# I2CRJ45X24.net
KiCad netlist of a schematic drawn in EAGLE
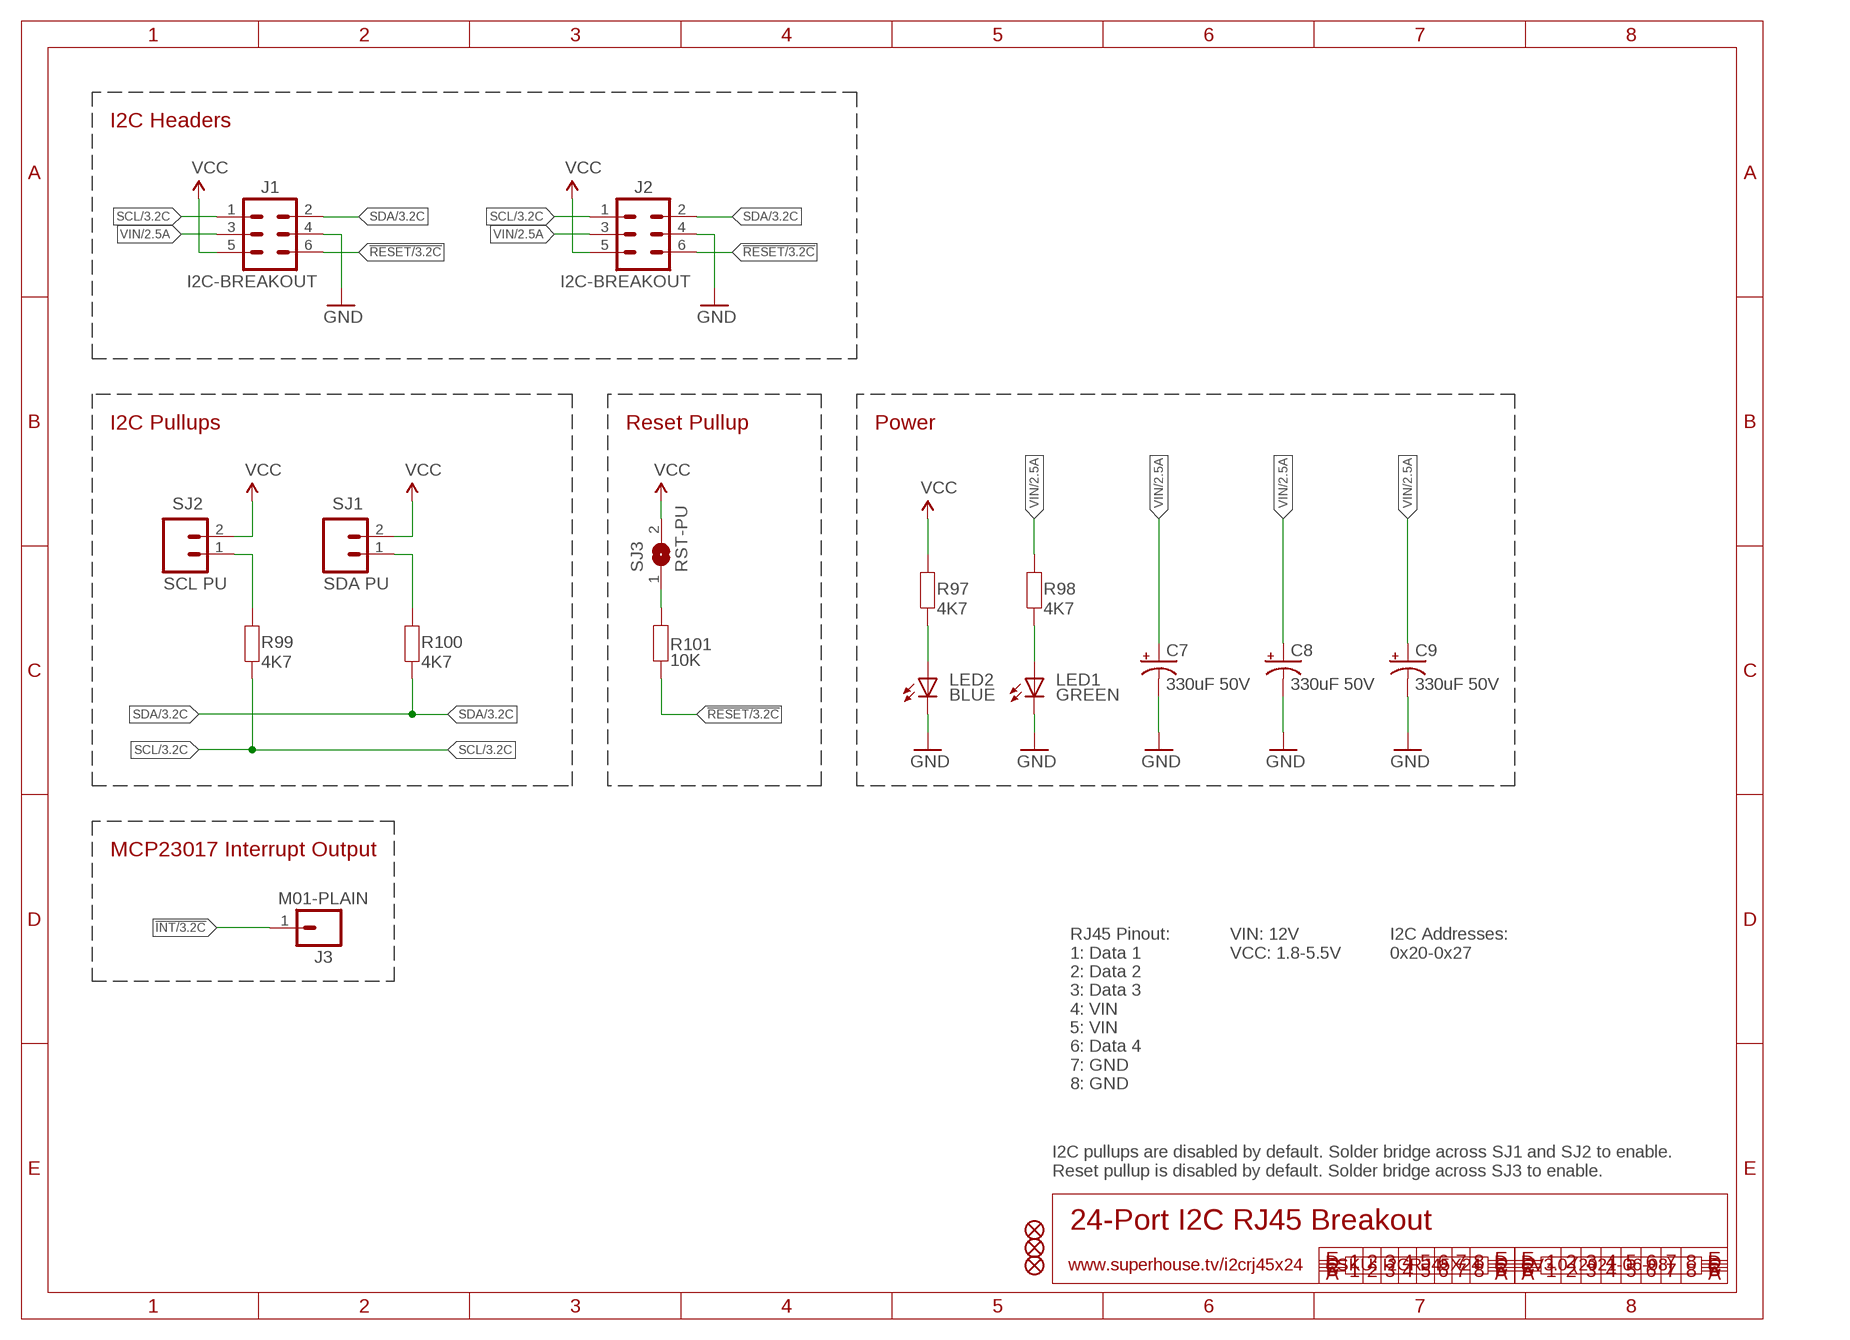
[diagram p0: schematic, sheet 1]
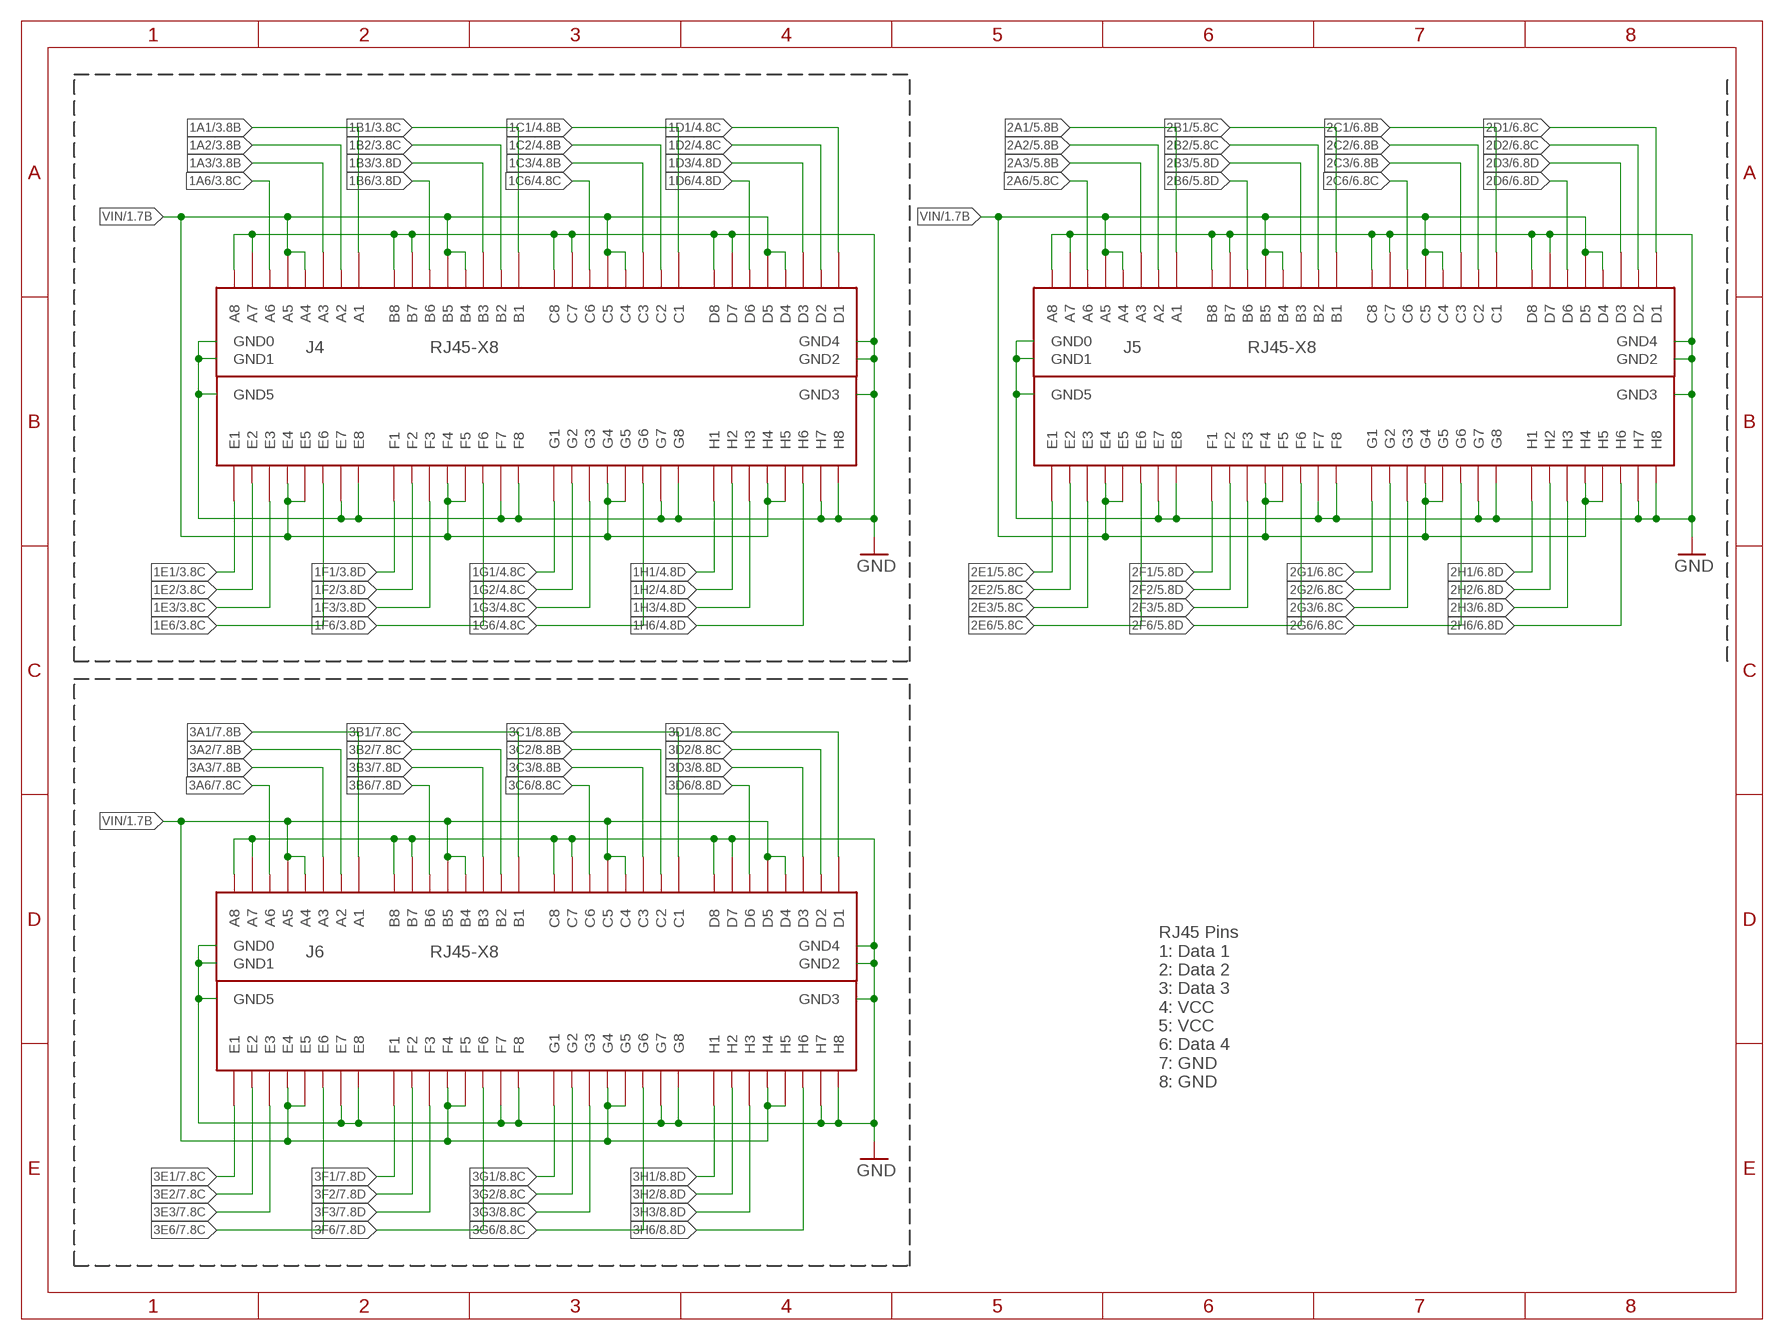
[diagram p1: schematic, sheet 2]
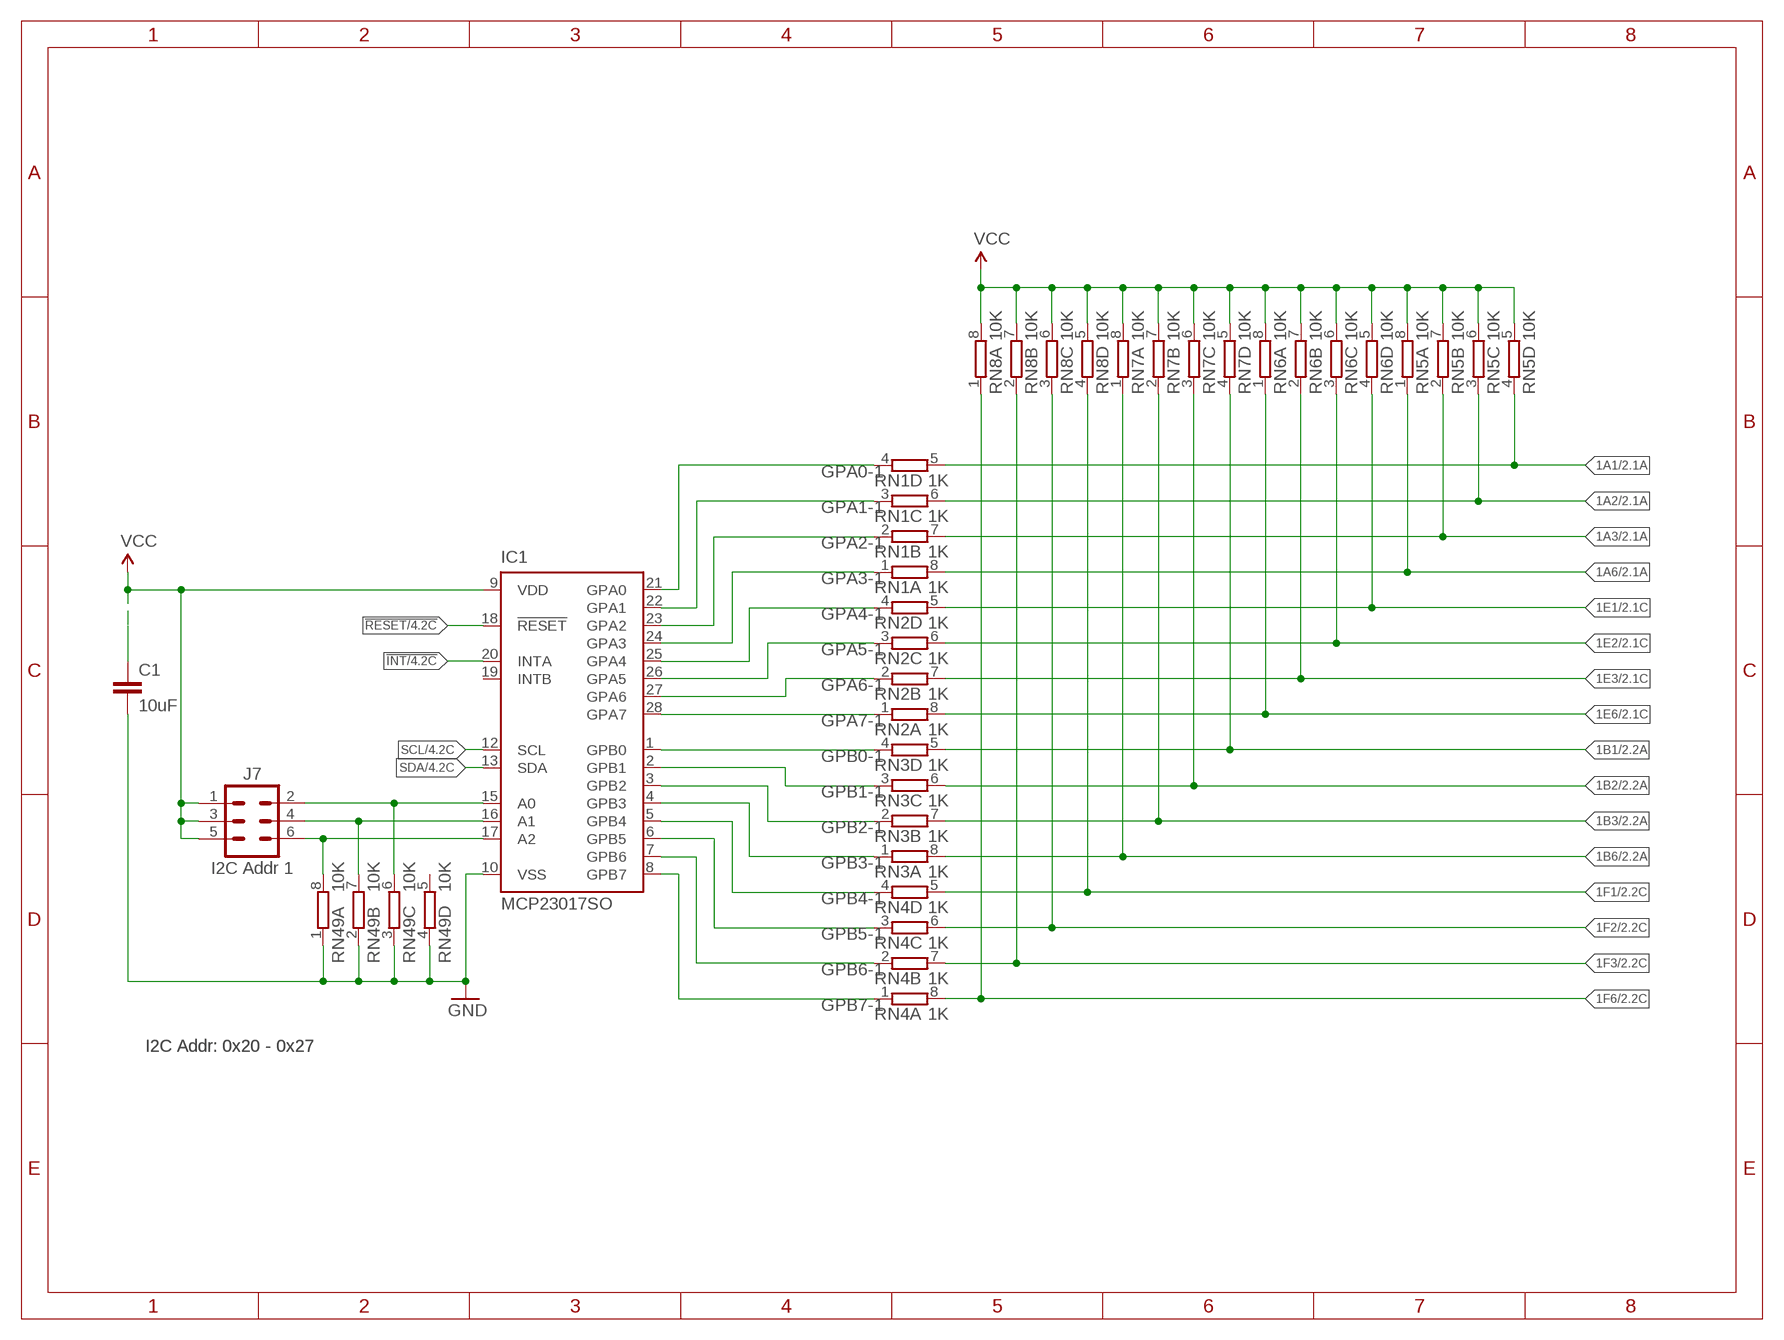
[diagram p2: schematic, sheet 3]
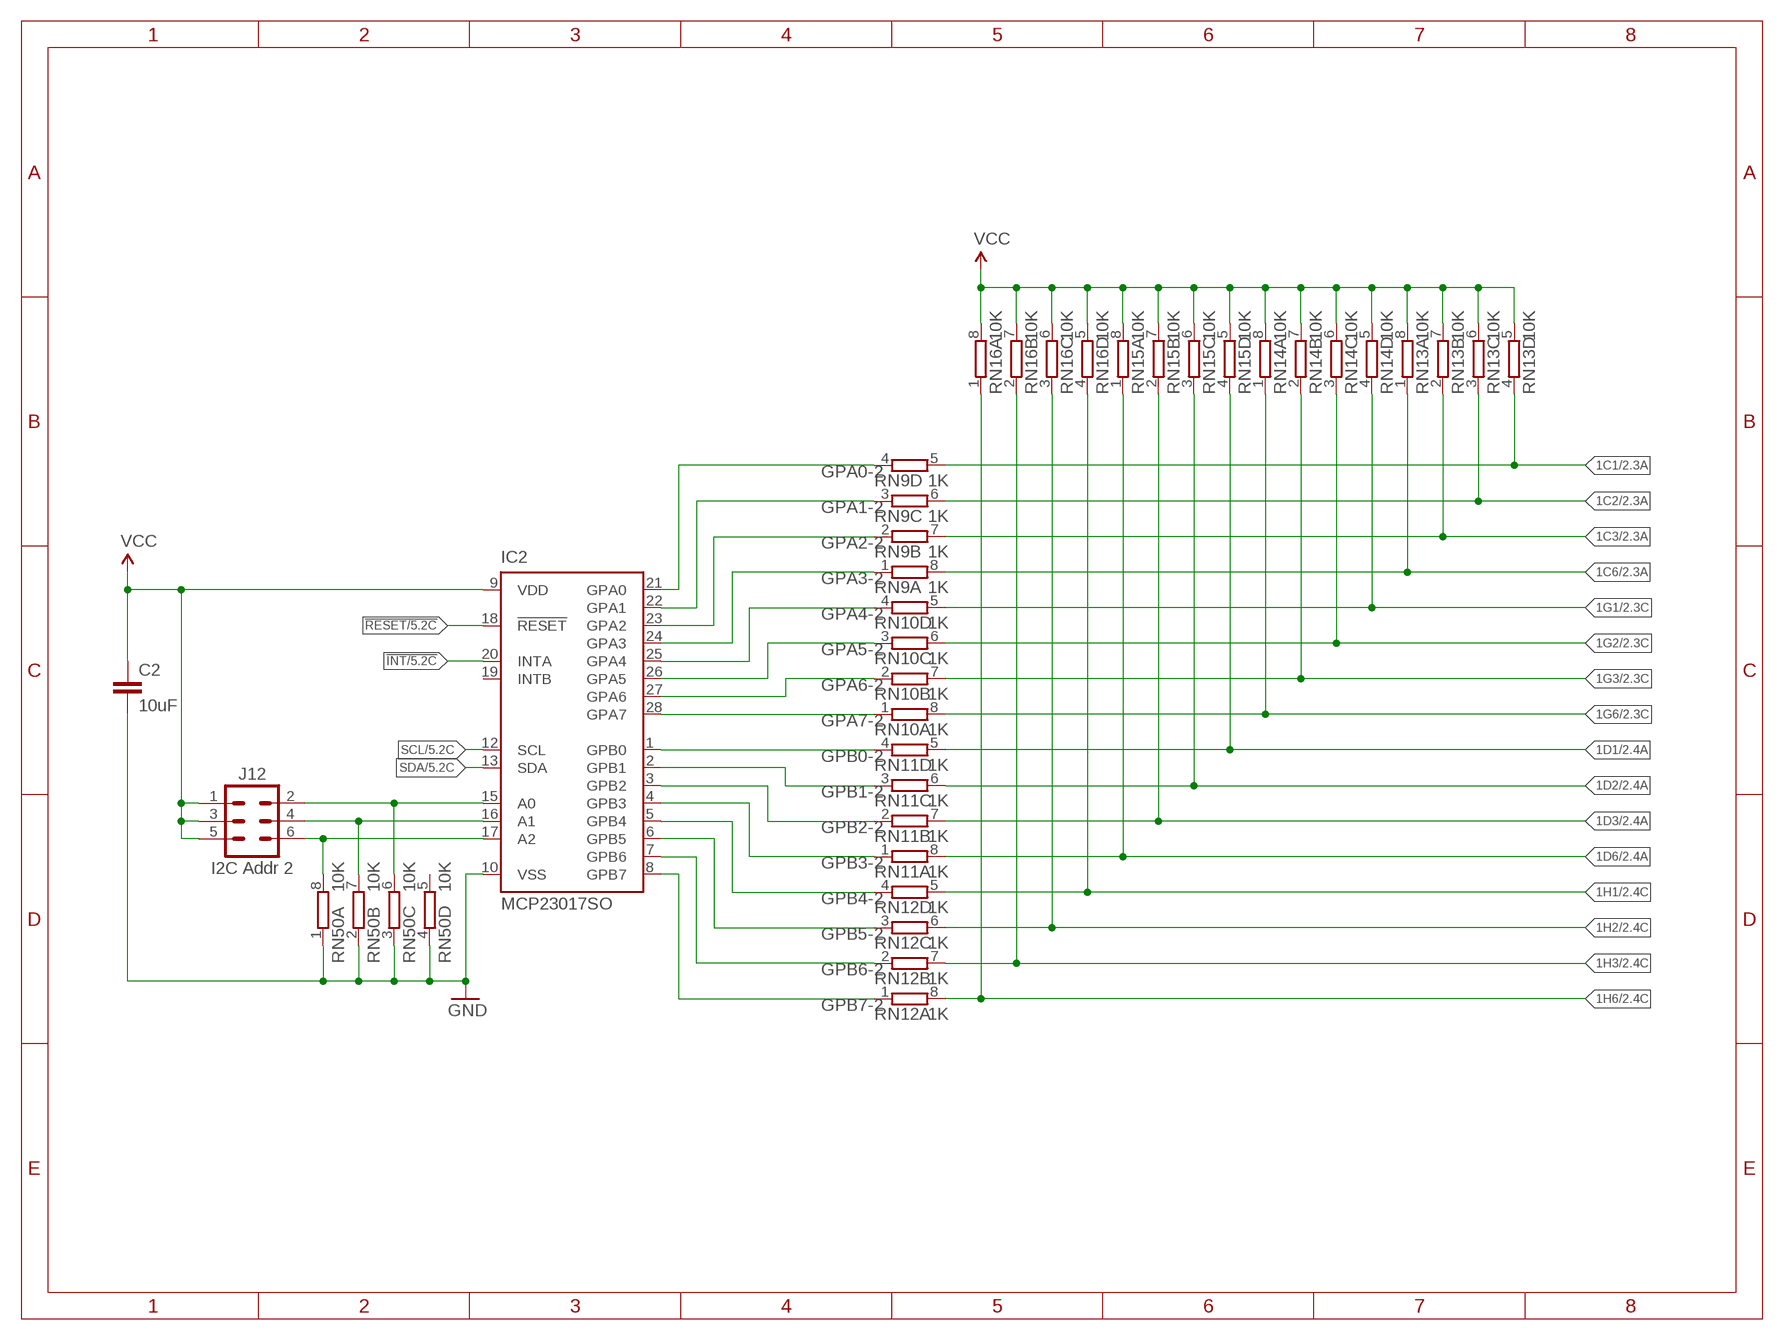
[diagram p3: schematic, sheet 4]
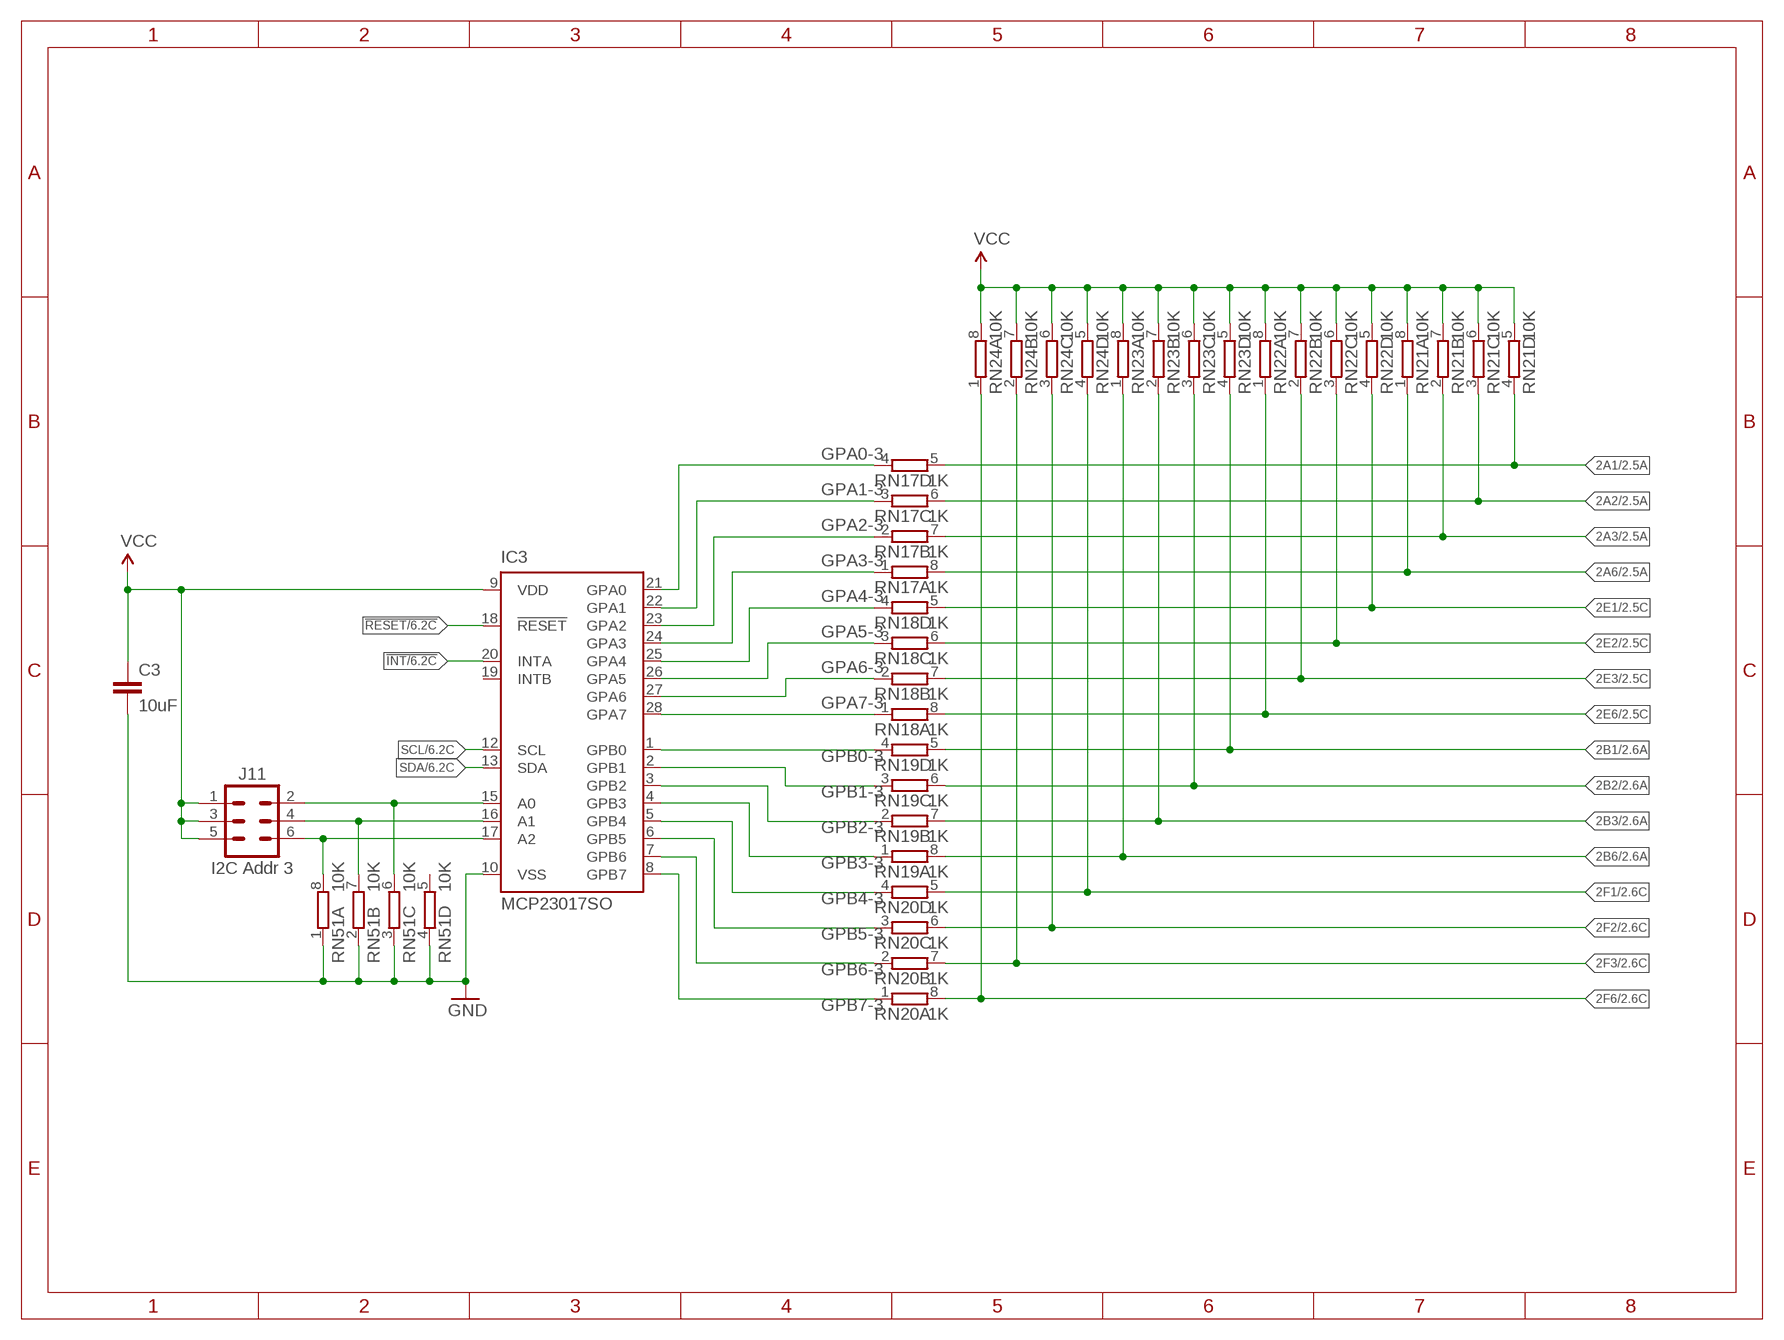
[diagram p4: schematic, sheet 5]
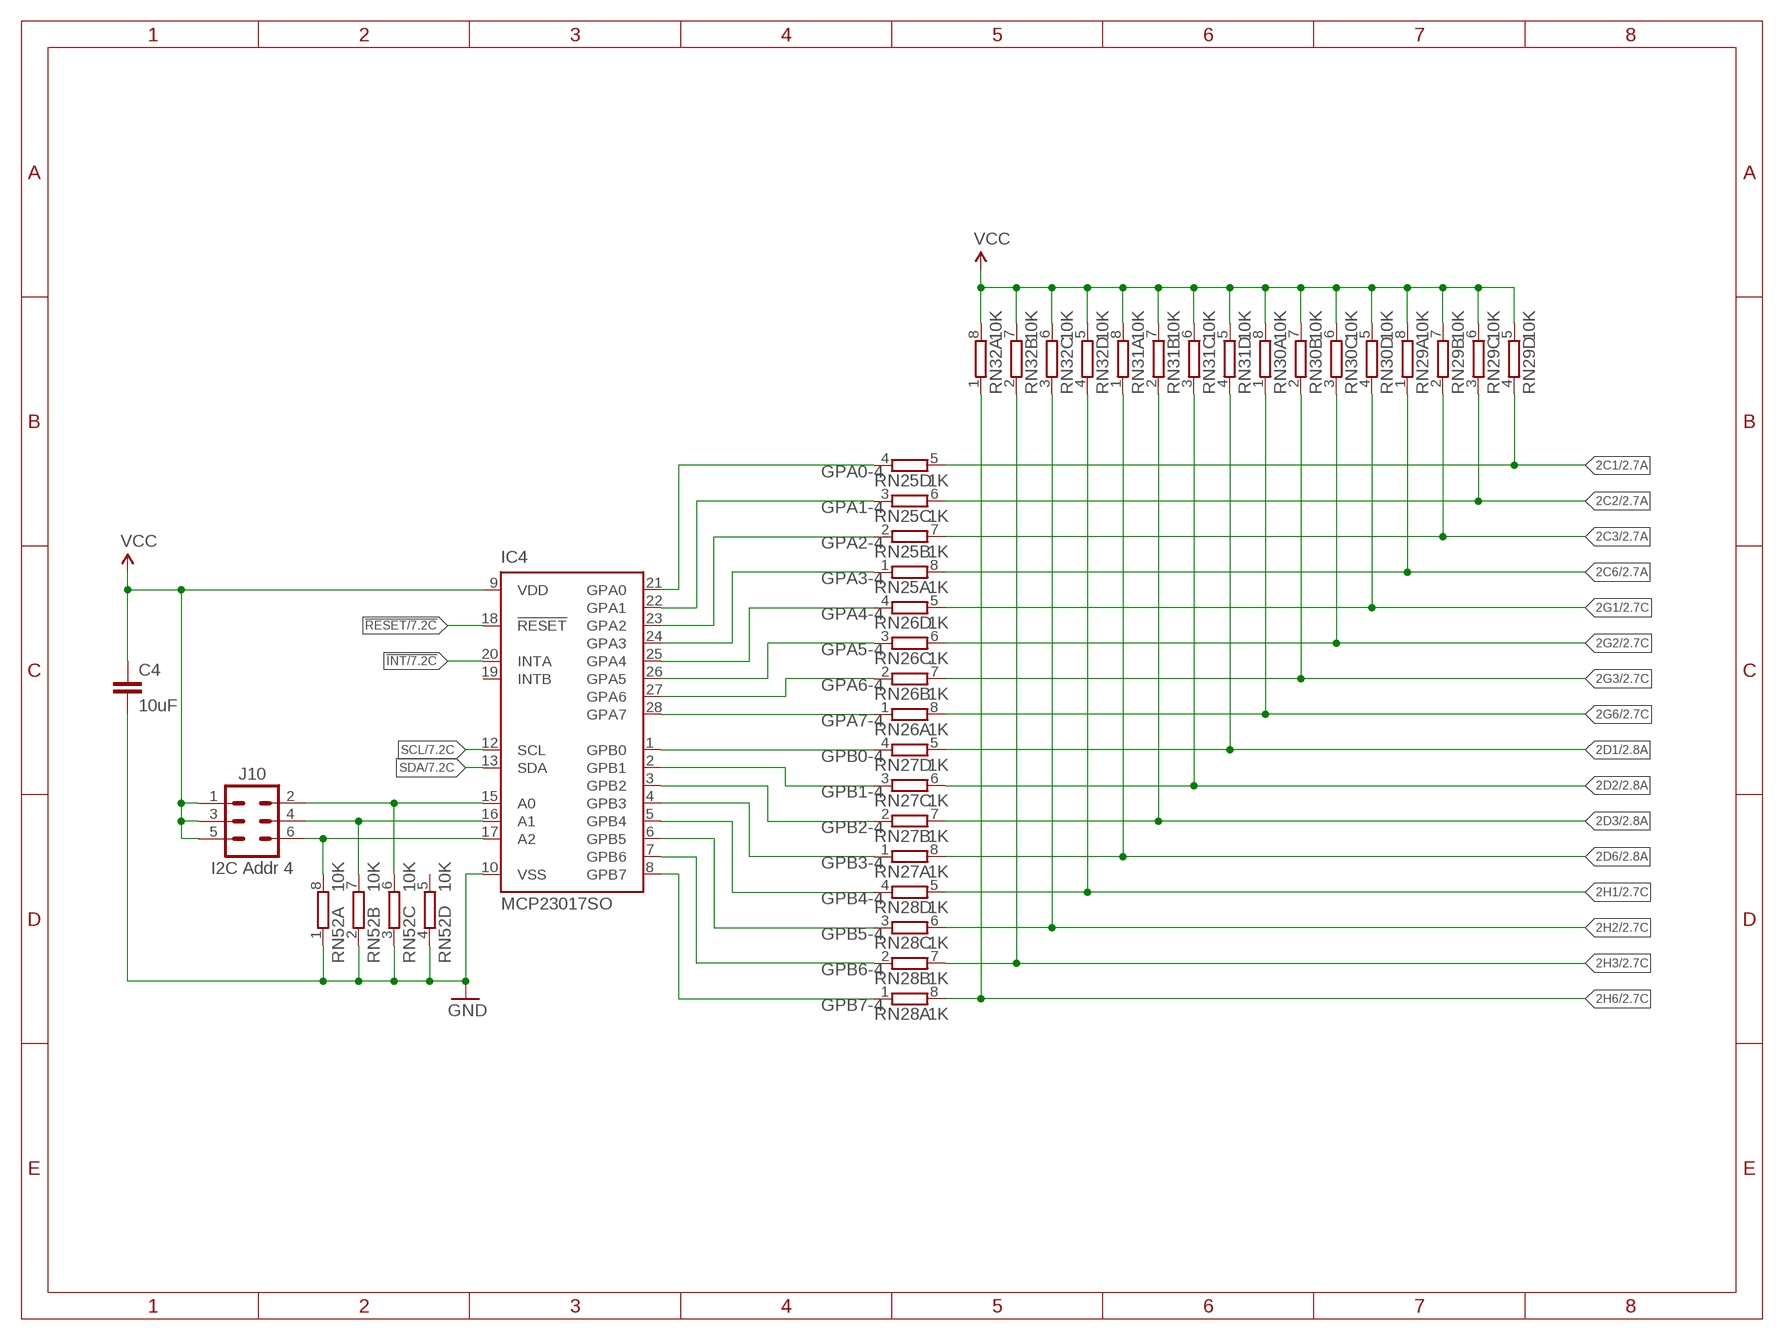
[diagram p5: schematic, sheet 6]
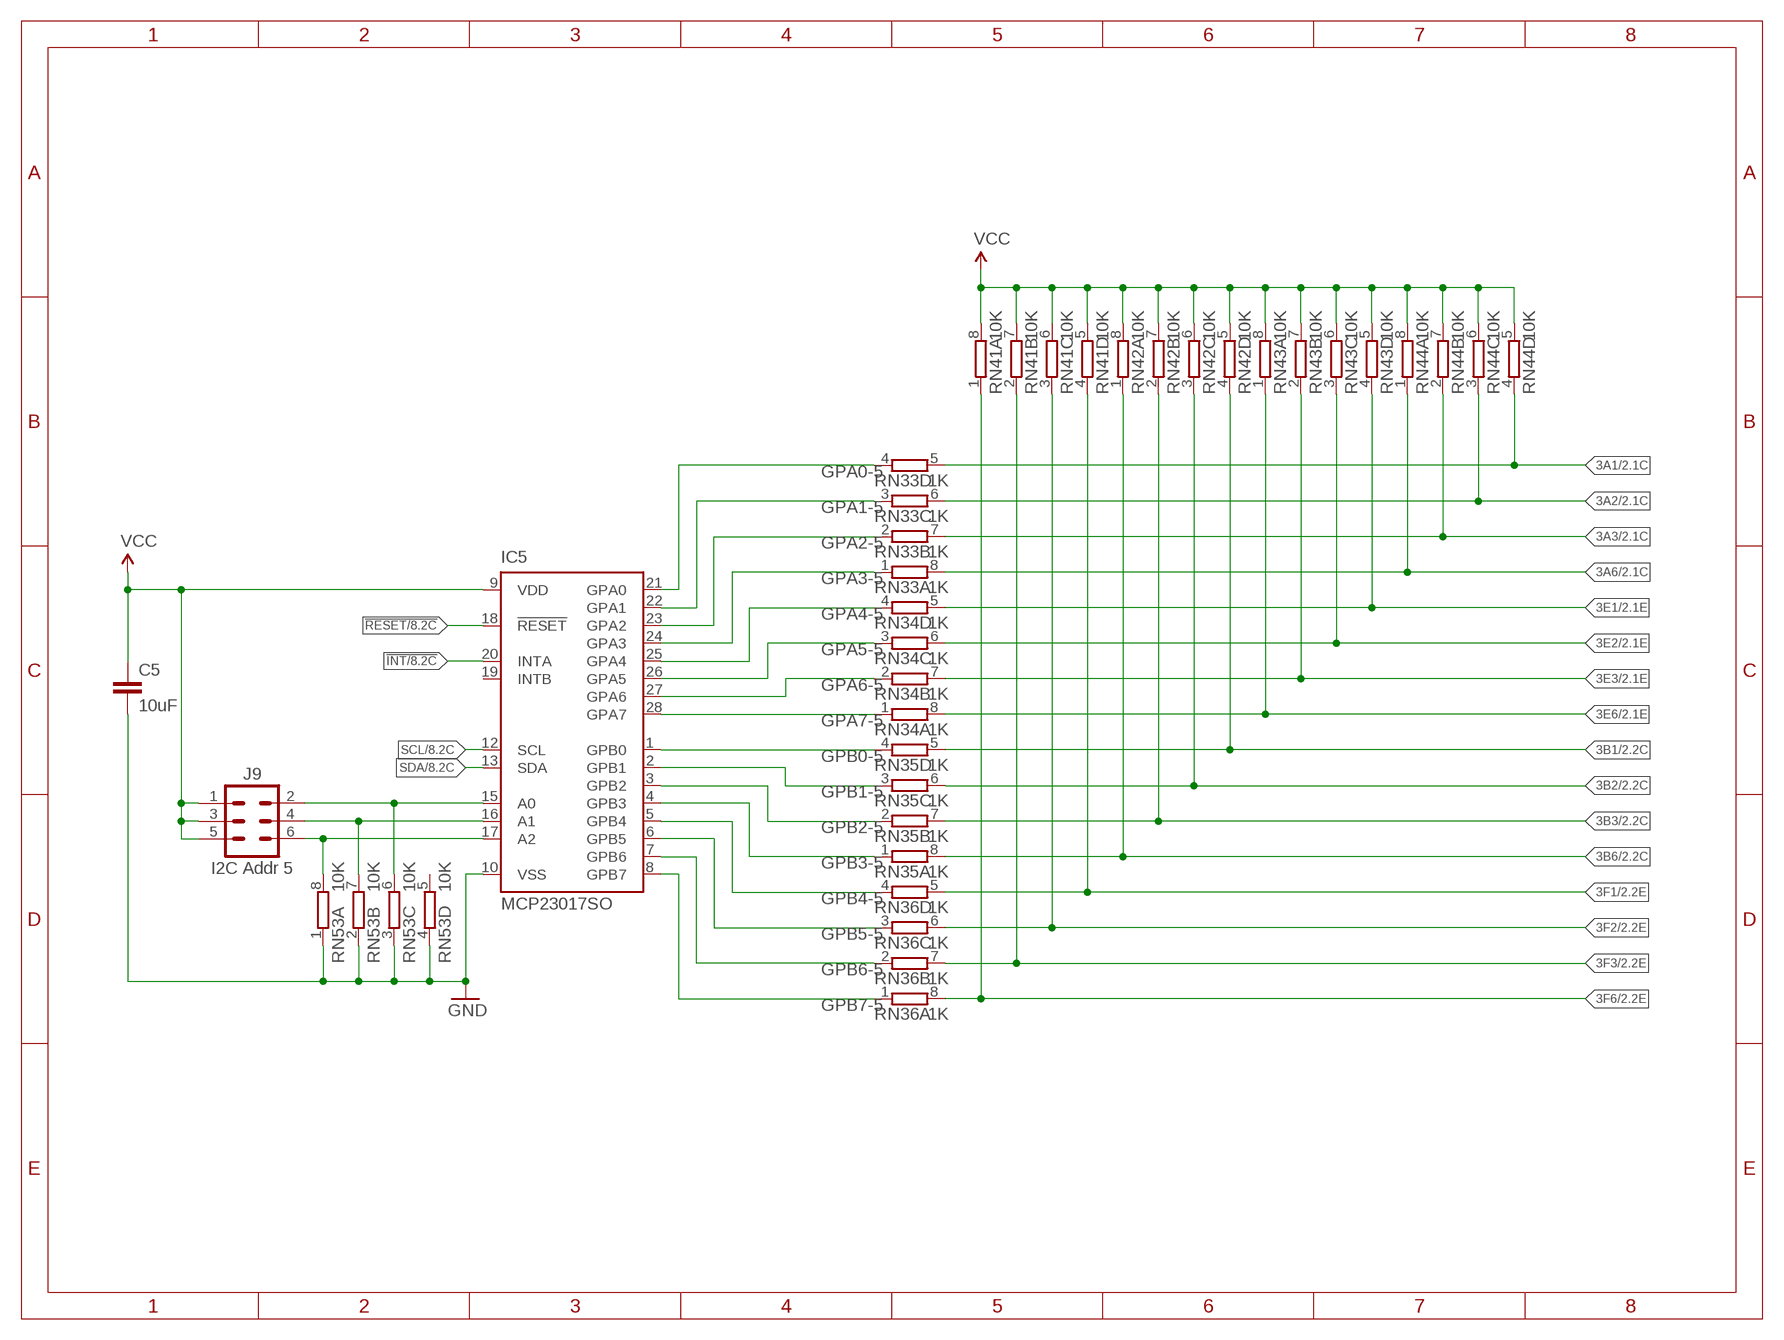
[diagram p6: schematic, sheet 7]
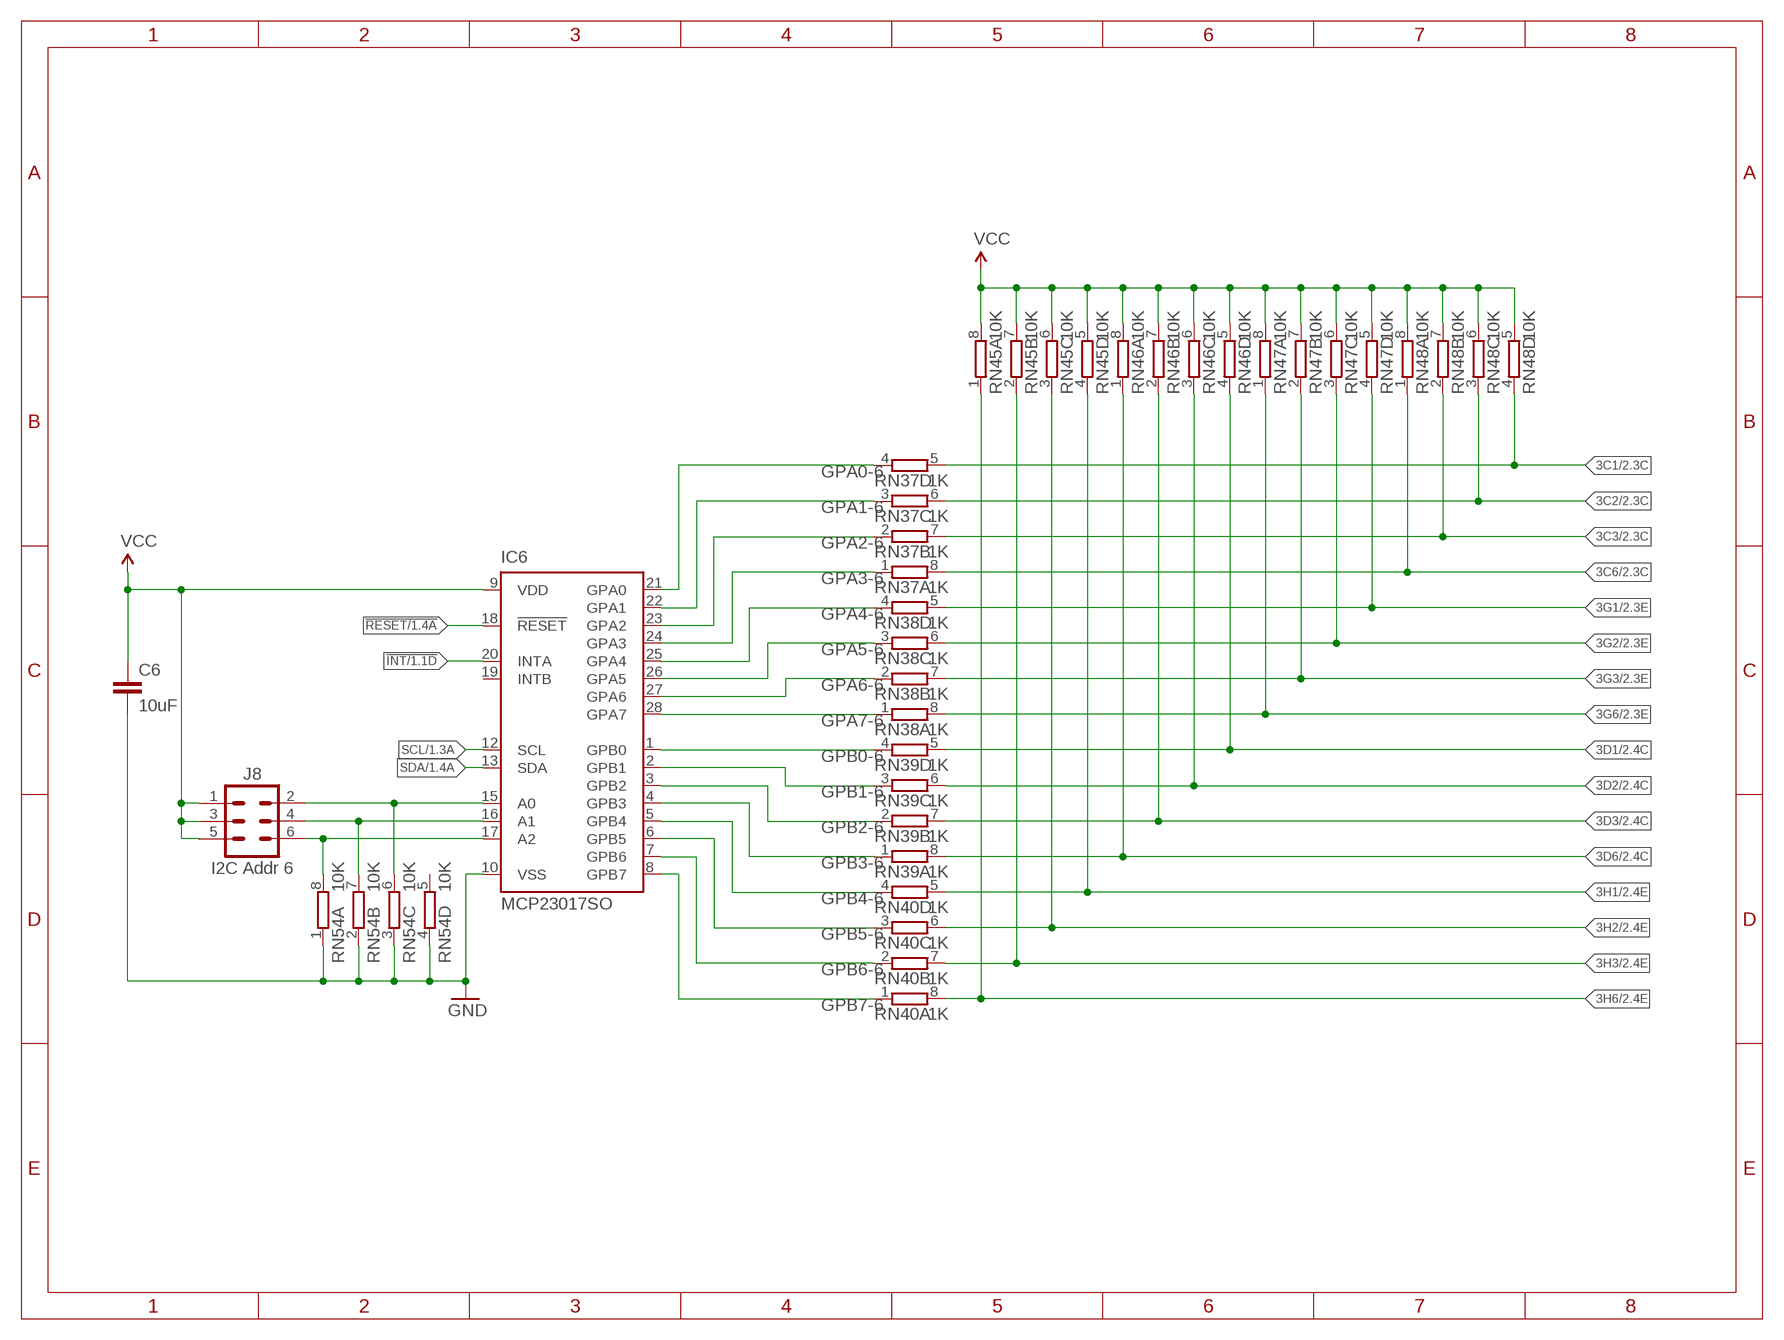
[diagram p7: schematic, sheet 8]

(export (version "E")
  (design (tool "Eeschema 10.0.6"))
  (components
    (comp (ref "C3")
      (value "10uF")
      (footprint "eagle-import:C0805")
      (libsource (lib "eagle-import") (part "CAP0805"))
    )
    (comp (ref "IC3")
      (value "MCP23017SO")
      (footprint "eagle-import:SO28W")
      (libsource (lib "eagle-import") (part "MCP23017SO"))
    )
    (comp (ref "J11")
      (value "I2C Addr 3")
      (footprint "eagle-import:2X03-P")
      (libsource (lib "eagle-import") (part "M02X3-PIN"))
    )
    (comp (ref "RN17")
      (value "1K")
      (footprint "eagle-import:CAY16")
      (libsource (lib "eagle-import") (part "4R-NCAY16"))
    )
    (comp (ref "RN18")
      (value "1K")
      (footprint "eagle-import:CAY16")
      (libsource (lib "eagle-import") (part "4R-NCAY16"))
    )
    (comp (ref "RN19")
      (value "1K")
      (footprint "eagle-import:CAY16")
      (libsource (lib "eagle-import") (part "4R-NCAY16"))
    )
    (comp (ref "RN20")
      (value "1K")
      (footprint "eagle-import:CAY16")
      (libsource (lib "eagle-import") (part "4R-NCAY16"))
    )
    (comp (ref "RN21")
      (value "10K")
      (footprint "eagle-import:CAY16")
      (libsource (lib "eagle-import") (part "4R-NCAY16"))
    )
    (comp (ref "RN22")
      (value "10K")
      (footprint "eagle-import:CAY16")
      (libsource (lib "eagle-import") (part "4R-NCAY16"))
    )
    (comp (ref "RN23")
      (value "10K")
      (footprint "eagle-import:CAY16")
      (libsource (lib "eagle-import") (part "4R-NCAY16"))
    )
    (comp (ref "RN24")
      (value "10K")
      (footprint "eagle-import:CAY16")
      (libsource (lib "eagle-import") (part "4R-NCAY16"))
    )
    (comp (ref "RN51")
      (value "10K")
      (footprint "eagle-import:CAY16")
      (libsource (lib "eagle-import") (part "4R-NCAY16"))
    )
    (comp (ref "C4")
      (value "10uF")
      (footprint "eagle-import:C0805")
      (libsource (lib "eagle-import") (part "CAP0805"))
    )
    (comp (ref "IC4")
      (value "MCP23017SO")
      (footprint "eagle-import:SO28W")
      (libsource (lib "eagle-import") (part "MCP23017SO"))
    )
    (comp (ref "J10")
      (value "I2C Addr 4")
      (footprint "eagle-import:2X03-P")
      (libsource (lib "eagle-import") (part "M02X3-PIN"))
    )
    (comp (ref "RN25")
      (value "1K")
      (footprint "eagle-import:CAY16")
      (libsource (lib "eagle-import") (part "4R-NCAY16"))
    )
    (comp (ref "RN26")
      (value "1K")
      (footprint "eagle-import:CAY16")
      (libsource (lib "eagle-import") (part "4R-NCAY16"))
    )
    (comp (ref "RN27")
      (value "1K")
      (footprint "eagle-import:CAY16")
      (libsource (lib "eagle-import") (part "4R-NCAY16"))
    )
    (comp (ref "RN28")
      (value "1K")
      (footprint "eagle-import:CAY16")
      (libsource (lib "eagle-import") (part "4R-NCAY16"))
    )
    (comp (ref "RN29")
      (value "10K")
      (footprint "eagle-import:CAY16")
      (libsource (lib "eagle-import") (part "4R-NCAY16"))
    )
    (comp (ref "RN30")
      (value "10K")
      (footprint "eagle-import:CAY16")
      (libsource (lib "eagle-import") (part "4R-NCAY16"))
    )
    (comp (ref "RN31")
      (value "10K")
      (footprint "eagle-import:CAY16")
      (libsource (lib "eagle-import") (part "4R-NCAY16"))
    )
    (comp (ref "RN32")
      (value "10K")
      (footprint "eagle-import:CAY16")
      (libsource (lib "eagle-import") (part "4R-NCAY16"))
    )
    (comp (ref "RN52")
      (value "10K")
      (footprint "eagle-import:CAY16")
      (libsource (lib "eagle-import") (part "4R-NCAY16"))
    )
    (comp (ref "C7")
      (value "330uF 50V")
      (footprint "eagle-import:PANASONIC_G")
      (libsource (lib "eagle-import") (part "CAP_POLG"))
    )
    (comp (ref "C8")
      (value "330uF 50V")
      (footprint "eagle-import:PANASONIC_G")
      (libsource (lib "eagle-import") (part "CAP_POLG"))
    )
    (comp (ref "C9")
      (value "330uF 50V")
      (footprint "eagle-import:PANASONIC_G")
      (libsource (lib "eagle-import") (part "CAP_POLG"))
    )
    (comp (ref "FID1")
      (value "FIDUCIAL1X2.5")
      (footprint "eagle-import:FIDUCIAL-1X2.5")
      (libsource (lib "eagle-import") (part "FIDUCIAL1X2.5"))
    )
    (comp (ref "FID2")
      (value "FIDUCIAL1X2.5")
      (footprint "eagle-import:FIDUCIAL-1X2.5")
      (libsource (lib "eagle-import") (part "FIDUCIAL1X2.5"))
    )
    (comp (ref "FID3")
      (value "FIDUCIAL1X2.5")
      (footprint "eagle-import:FIDUCIAL-1X2.5")
      (libsource (lib "eagle-import") (part "FIDUCIAL1X2.5"))
    )
    (comp (ref "J1")
      (value "I2C-BREAKOUT")
      (footprint "eagle-import:2X3-2.54-SHROUDED")
      (libsource (lib "eagle-import") (part "M02X3-SHROUDED"))
    )
    (comp (ref "J2")
      (value "I2C-BREAKOUT")
      (footprint "eagle-import:2X3-2.54-SHROUDED")
      (libsource (lib "eagle-import") (part "M02X3-SHROUDED"))
    )
    (comp (ref "J3")
      (value "M01-PLAIN")
      (footprint "eagle-import:1X01")
      (libsource (lib "eagle-import") (part "M01-PLAIN"))
    )
    (comp (ref "LED1")
      (value "GREEN")
      (footprint "eagle-import:LED-0603")
      (libsource (lib "eagle-import") (part "LED0603"))
    )
    (comp (ref "LED2")
      (value "BLUE")
      (footprint "eagle-import:LED-0603")
      (libsource (lib "eagle-import") (part "LED0603"))
    )
    (comp (ref "R97")
      (value "4K7")
      (footprint "eagle-import:R0603")
      (libsource (lib "eagle-import") (part "RESISTOR0603"))
    )
    (comp (ref "R98")
      (value "4K7")
      (footprint "eagle-import:R0603")
      (libsource (lib "eagle-import") (part "RESISTOR0603"))
    )
    (comp (ref "R99")
      (value "4K7")
      (footprint "eagle-import:R0603")
      (libsource (lib "eagle-import") (part "RESISTOR0603"))
    )
    (comp (ref "R100")
      (value "4K7")
      (footprint "eagle-import:R0603")
      (libsource (lib "eagle-import") (part "RESISTOR0603"))
    )
    (comp (ref "R101")
      (value "10K")
      (footprint "eagle-import:R0603")
      (libsource (lib "eagle-import") (part "RESISTOR0603"))
    )
    (comp (ref "SJ1")
      (value "SDA PU")
      (footprint "eagle-import:1X02-P")
      (libsource (lib "eagle-import") (part "M02-PIN"))
    )
    (comp (ref "SJ2")
      (value "SCL PU")
      (footprint "eagle-import:1X02-P")
      (libsource (lib "eagle-import") (part "M02-PIN"))
    )
    (comp (ref "SJ3")
      (value "RST-PU")
      (footprint "eagle-import:SJ")
      (libsource (lib "eagle-import") (part "SJ-NORMAL"))
    )
    (comp (ref "C6")
      (value "10uF")
      (footprint "eagle-import:C0805")
      (libsource (lib "eagle-import") (part "CAP0805"))
    )
    (comp (ref "IC6")
      (value "MCP23017SO")
      (footprint "eagle-import:SO28W")
      (libsource (lib "eagle-import") (part "MCP23017SO"))
    )
    (comp (ref "J8")
      (value "I2C Addr 6")
      (footprint "eagle-import:2X03-P")
      (libsource (lib "eagle-import") (part "M02X3-PIN"))
    )
    (comp (ref "RN37")
      (value "1K")
      (footprint "eagle-import:CAY16")
      (libsource (lib "eagle-import") (part "4R-NCAY16"))
    )
    (comp (ref "RN38")
      (value "1K")
      (footprint "eagle-import:CAY16")
      (libsource (lib "eagle-import") (part "4R-NCAY16"))
    )
    (comp (ref "RN39")
      (value "1K")
      (footprint "eagle-import:CAY16")
      (libsource (lib "eagle-import") (part "4R-NCAY16"))
    )
    (comp (ref "RN40")
      (value "1K")
      (footprint "eagle-import:CAY16")
      (libsource (lib "eagle-import") (part "4R-NCAY16"))
    )
    (comp (ref "RN45")
      (value "10K")
      (footprint "eagle-import:CAY16")
      (libsource (lib "eagle-import") (part "4R-NCAY16"))
    )
    (comp (ref "RN46")
      (value "10K")
      (footprint "eagle-import:CAY16")
      (libsource (lib "eagle-import") (part "4R-NCAY16"))
    )
    (comp (ref "RN47")
      (value "10K")
      (footprint "eagle-import:CAY16")
      (libsource (lib "eagle-import") (part "4R-NCAY16"))
    )
    (comp (ref "RN48")
      (value "10K")
      (footprint "eagle-import:CAY16")
      (libsource (lib "eagle-import") (part "4R-NCAY16"))
    )
    (comp (ref "RN54")
      (value "10K")
      (footprint "eagle-import:CAY16")
      (libsource (lib "eagle-import") (part "4R-NCAY16"))
    )
    (comp (ref "C5")
      (value "10uF")
      (footprint "eagle-import:C0805")
      (libsource (lib "eagle-import") (part "CAP0805"))
    )
    (comp (ref "IC5")
      (value "MCP23017SO")
      (footprint "eagle-import:SO28W")
      (libsource (lib "eagle-import") (part "MCP23017SO"))
    )
    (comp (ref "J9")
      (value "I2C Addr 5")
      (footprint "eagle-import:2X03-P")
      (libsource (lib "eagle-import") (part "M02X3-PIN"))
    )
    (comp (ref "RN33")
      (value "1K")
      (footprint "eagle-import:CAY16")
      (libsource (lib "eagle-import") (part "4R-NCAY16"))
    )
    (comp (ref "RN34")
      (value "1K")
      (footprint "eagle-import:CAY16")
      (libsource (lib "eagle-import") (part "4R-NCAY16"))
    )
    (comp (ref "RN35")
      (value "1K")
      (footprint "eagle-import:CAY16")
      (libsource (lib "eagle-import") (part "4R-NCAY16"))
    )
    (comp (ref "RN36")
      (value "1K")
      (footprint "eagle-import:CAY16")
      (libsource (lib "eagle-import") (part "4R-NCAY16"))
    )
    (comp (ref "RN41")
      (value "10K")
      (footprint "eagle-import:CAY16")
      (libsource (lib "eagle-import") (part "4R-NCAY16"))
    )
    (comp (ref "RN42")
      (value "10K")
      (footprint "eagle-import:CAY16")
      (libsource (lib "eagle-import") (part "4R-NCAY16"))
    )
    (comp (ref "RN43")
      (value "10K")
      (footprint "eagle-import:CAY16")
      (libsource (lib "eagle-import") (part "4R-NCAY16"))
    )
    (comp (ref "RN44")
      (value "10K")
      (footprint "eagle-import:CAY16")
      (libsource (lib "eagle-import") (part "4R-NCAY16"))
    )
    (comp (ref "RN53")
      (value "10K")
      (footprint "eagle-import:CAY16")
      (libsource (lib "eagle-import") (part "4R-NCAY16"))
    )
    (comp (ref "J4")
      (value "RJ45-X8")
      (footprint "eagle-import:RJ45-2X4")
      (libsource (lib "eagle-import") (part "RJ45-X8"))
    )
    (comp (ref "J5")
      (value "RJ45-X8")
      (footprint "eagle-import:RJ45-2X4")
      (libsource (lib "eagle-import") (part "RJ45-X8"))
    )
    (comp (ref "J6")
      (value "RJ45-X8")
      (footprint "eagle-import:RJ45-2X4")
      (libsource (lib "eagle-import") (part "RJ45-X8"))
    )
    (comp (ref "C2")
      (value "10uF")
      (footprint "eagle-import:C0805")
      (libsource (lib "eagle-import") (part "CAP0805"))
    )
    (comp (ref "IC2")
      (value "MCP23017SO")
      (footprint "eagle-import:SO28W")
      (libsource (lib "eagle-import") (part "MCP23017SO"))
    )
    (comp (ref "J12")
      (value "I2C Addr 2")
      (footprint "eagle-import:2X03-P")
      (libsource (lib "eagle-import") (part "M02X3-PIN"))
    )
    (comp (ref "RN9")
      (value "1K")
      (footprint "eagle-import:CAY16")
      (libsource (lib "eagle-import") (part "4R-NCAY16"))
    )
    (comp (ref "RN10")
      (value "1K")
      (footprint "eagle-import:CAY16")
      (libsource (lib "eagle-import") (part "4R-NCAY16"))
    )
    (comp (ref "RN11")
      (value "1K")
      (footprint "eagle-import:CAY16")
      (libsource (lib "eagle-import") (part "4R-NCAY16"))
    )
    (comp (ref "RN12")
      (value "1K")
      (footprint "eagle-import:CAY16")
      (libsource (lib "eagle-import") (part "4R-NCAY16"))
    )
    (comp (ref "RN13")
      (value "10K")
      (footprint "eagle-import:CAY16")
      (libsource (lib "eagle-import") (part "4R-NCAY16"))
    )
    (comp (ref "RN14")
      (value "10K")
      (footprint "eagle-import:CAY16")
      (libsource (lib "eagle-import") (part "4R-NCAY16"))
    )
    (comp (ref "RN15")
      (value "10K")
      (footprint "eagle-import:CAY16")
      (libsource (lib "eagle-import") (part "4R-NCAY16"))
    )
    (comp (ref "RN16")
      (value "10K")
      (footprint "eagle-import:CAY16")
      (libsource (lib "eagle-import") (part "4R-NCAY16"))
    )
    (comp (ref "RN50")
      (value "10K")
      (footprint "eagle-import:CAY16")
      (libsource (lib "eagle-import") (part "4R-NCAY16"))
    )
    (comp (ref "C1")
      (value "10uF")
      (footprint "eagle-import:C0805")
      (libsource (lib "eagle-import") (part "CAP0805"))
    )
    (comp (ref "IC1")
      (value "MCP23017SO")
      (footprint "eagle-import:SO28W")
      (libsource (lib "eagle-import") (part "MCP23017SO"))
    )
    (comp (ref "J7")
      (value "I2C Addr 1")
      (footprint "eagle-import:2X03-P")
      (libsource (lib "eagle-import") (part "M02X3-PIN"))
    )
    (comp (ref "RN1")
      (value "1K")
      (footprint "eagle-import:CAY16")
      (libsource (lib "eagle-import") (part "4R-NCAY16"))
    )
    (comp (ref "RN2")
      (value "1K")
      (footprint "eagle-import:CAY16")
      (libsource (lib "eagle-import") (part "4R-NCAY16"))
    )
    (comp (ref "RN3")
      (value "1K")
      (footprint "eagle-import:CAY16")
      (libsource (lib "eagle-import") (part "4R-NCAY16"))
    )
    (comp (ref "RN4")
      (value "1K")
      (footprint "eagle-import:CAY16")
      (libsource (lib "eagle-import") (part "4R-NCAY16"))
    )
    (comp (ref "RN5")
      (value "10K")
      (footprint "eagle-import:CAY16")
      (libsource (lib "eagle-import") (part "4R-NCAY16"))
    )
    (comp (ref "RN6")
      (value "10K")
      (footprint "eagle-import:CAY16")
      (libsource (lib "eagle-import") (part "4R-NCAY16"))
    )
    (comp (ref "RN7")
      (value "10K")
      (footprint "eagle-import:CAY16")
      (libsource (lib "eagle-import") (part "4R-NCAY16"))
    )
    (comp (ref "RN8")
      (value "10K")
      (footprint "eagle-import:CAY16")
      (libsource (lib "eagle-import") (part "4R-NCAY16"))
    )
    (comp (ref "RN49")
      (value "10K")
      (footprint "eagle-import:CAY16")
      (libsource (lib "eagle-import") (part "4R-NCAY16"))
    )
  )
  (nets
    (net (code "1") (name "1A1") (class "Default")
      (node (ref "J4") (pin "A1") (pinfunction "A1_A1") (pintype "bidirectional"))
      (node (ref "RN1") (pin "5") (pinfunction "2_5") (pintype "passive"))
      (node (ref "RN5") (pin "4") (pinfunction "1_4") (pintype "passive"))
    )
    (net (code "2") (name "1A2") (class "Default")
      (node (ref "J4") (pin "A2") (pinfunction "A2_A2") (pintype "bidirectional"))
      (node (ref "RN1") (pin "6") (pinfunction "2_6") (pintype "passive"))
      (node (ref "RN5") (pin "3") (pinfunction "1_3") (pintype "passive"))
    )
    (net (code "3") (name "1A3") (class "Default")
      (node (ref "J4") (pin "A3") (pinfunction "A3_A3") (pintype "bidirectional"))
      (node (ref "RN1") (pin "7") (pinfunction "2_7") (pintype "passive"))
      (node (ref "RN5") (pin "2") (pinfunction "1_2") (pintype "passive"))
    )
    (net (code "4") (name "1A6") (class "Default")
      (node (ref "J4") (pin "A6") (pinfunction "A6_A6") (pintype "bidirectional"))
      (node (ref "RN1") (pin "8") (pinfunction "2_8") (pintype "passive"))
      (node (ref "RN5") (pin "1") (pinfunction "1_1") (pintype "passive"))
    )
    (net (code "5") (name "1B1") (class "Default")
      (node (ref "J4") (pin "B1") (pinfunction "B1_B1") (pintype "bidirectional"))
      (node (ref "RN3") (pin "5") (pinfunction "2_5") (pintype "passive"))
      (node (ref "RN7") (pin "4") (pinfunction "1_4") (pintype "passive"))
    )
    (net (code "6") (name "1B2") (class "Default")
      (node (ref "J4") (pin "B2") (pinfunction "B2_B2") (pintype "bidirectional"))
      (node (ref "RN3") (pin "6") (pinfunction "2_6") (pintype "passive"))
      (node (ref "RN7") (pin "3") (pinfunction "1_3") (pintype "passive"))
    )
    (net (code "7") (name "1B3") (class "Default")
      (node (ref "J4") (pin "B3") (pinfunction "B3_B3") (pintype "bidirectional"))
      (node (ref "RN3") (pin "7") (pinfunction "2_7") (pintype "passive"))
      (node (ref "RN7") (pin "2") (pinfunction "1_2") (pintype "passive"))
    )
    (net (code "8") (name "1B6") (class "Default")
      (node (ref "J4") (pin "B6") (pinfunction "B6_B6") (pintype "bidirectional"))
      (node (ref "RN3") (pin "8") (pinfunction "2_8") (pintype "passive"))
      (node (ref "RN7") (pin "1") (pinfunction "1_1") (pintype "passive"))
    )
    (net (code "9") (name "1C1") (class "Default")
      (node (ref "J4") (pin "C1") (pinfunction "C1_C1") (pintype "bidirectional"))
      (node (ref "RN13") (pin "4") (pinfunction "1_4") (pintype "passive"))
      (node (ref "RN9") (pin "5") (pinfunction "2_5") (pintype "passive"))
    )
    (net (code "10") (name "1C2") (class "Default")
      (node (ref "J4") (pin "C2") (pinfunction "C2_C2") (pintype "bidirectional"))
      (node (ref "RN13") (pin "3") (pinfunction "1_3") (pintype "passive"))
      (node (ref "RN9") (pin "6") (pinfunction "2_6") (pintype "passive"))
    )
    (net (code "11") (name "1C3") (class "Default")
      (node (ref "J4") (pin "C3") (pinfunction "C3_C3") (pintype "bidirectional"))
      (node (ref "RN13") (pin "2") (pinfunction "1_2") (pintype "passive"))
      (node (ref "RN9") (pin "7") (pinfunction "2_7") (pintype "passive"))
    )
    (net (code "12") (name "1C6") (class "Default")
      (node (ref "J4") (pin "C6") (pinfunction "C6_C6") (pintype "bidirectional"))
      (node (ref "RN13") (pin "1") (pinfunction "1_1") (pintype "passive"))
      (node (ref "RN9") (pin "8") (pinfunction "2_8") (pintype "passive"))
    )
    (net (code "13") (name "1D1") (class "Default")
      (node (ref "J4") (pin "D1") (pinfunction "D1_D1") (pintype "bidirectional"))
      (node (ref "RN11") (pin "5") (pinfunction "2_5") (pintype "passive"))
      (node (ref "RN15") (pin "4") (pinfunction "1_4") (pintype "passive"))
    )
    (net (code "14") (name "1D2") (class "Default")
      (node (ref "J4") (pin "D2") (pinfunction "D2_D2") (pintype "bidirectional"))
      (node (ref "RN11") (pin "6") (pinfunction "2_6") (pintype "passive"))
      (node (ref "RN15") (pin "3") (pinfunction "1_3") (pintype "passive"))
    )
    (net (code "15") (name "1D3") (class "Default")
      (node (ref "J4") (pin "D3") (pinfunction "D3_D3") (pintype "bidirectional"))
      (node (ref "RN11") (pin "7") (pinfunction "2_7") (pintype "passive"))
      (node (ref "RN15") (pin "2") (pinfunction "1_2") (pintype "passive"))
    )
    (net (code "16") (name "1D6") (class "Default")
      (node (ref "J4") (pin "D6") (pinfunction "D6_D6") (pintype "bidirectional"))
      (node (ref "RN11") (pin "8") (pinfunction "2_8") (pintype "passive"))
      (node (ref "RN15") (pin "1") (pinfunction "1_1") (pintype "passive"))
    )
    (net (code "17") (name "1E1") (class "Default")
      (node (ref "J4") (pin "E1") (pinfunction "E1_E1") (pintype "bidirectional"))
      (node (ref "RN2") (pin "5") (pinfunction "2_5") (pintype "passive"))
      (node (ref "RN6") (pin "4") (pinfunction "1_4") (pintype "passive"))
    )
    (net (code "18") (name "1E2") (class "Default")
      (node (ref "J4") (pin "E2") (pinfunction "E2_E2") (pintype "bidirectional"))
      (node (ref "RN2") (pin "6") (pinfunction "2_6") (pintype "passive"))
      (node (ref "RN6") (pin "3") (pinfunction "1_3") (pintype "passive"))
    )
    (net (code "19") (name "1E3") (class "Default")
      (node (ref "J4") (pin "E3") (pinfunction "E3_E3") (pintype "bidirectional"))
      (node (ref "RN2") (pin "7") (pinfunction "2_7") (pintype "passive"))
      (node (ref "RN6") (pin "2") (pinfunction "1_2") (pintype "passive"))
    )
    (net (code "20") (name "1E6") (class "Default")
      (node (ref "J4") (pin "E6") (pinfunction "E6_E6") (pintype "bidirectional"))
      (node (ref "RN2") (pin "8") (pinfunction "2_8") (pintype "passive"))
      (node (ref "RN6") (pin "1") (pinfunction "1_1") (pintype "passive"))
    )
    (net (code "21") (name "1F1") (class "Default")
      (node (ref "J4") (pin "F1") (pinfunction "F1_F1") (pintype "bidirectional"))
      (node (ref "RN4") (pin "5") (pinfunction "2_5") (pintype "passive"))
      (node (ref "RN8") (pin "4") (pinfunction "1_4") (pintype "passive"))
    )
    (net (code "22") (name "1F2") (class "Default")
      (node (ref "J4") (pin "F2") (pinfunction "F2_F2") (pintype "bidirectional"))
      (node (ref "RN4") (pin "6") (pinfunction "2_6") (pintype "passive"))
      (node (ref "RN8") (pin "3") (pinfunction "1_3") (pintype "passive"))
    )
    (net (code "23") (name "1F3") (class "Default")
      (node (ref "J4") (pin "F3") (pinfunction "F3_F3") (pintype "bidirectional"))
      (node (ref "RN4") (pin "7") (pinfunction "2_7") (pintype "passive"))
      (node (ref "RN8") (pin "2") (pinfunction "1_2") (pintype "passive"))
    )
    (net (code "24") (name "1F6") (class "Default")
      (node (ref "J4") (pin "F6") (pinfunction "F6_F6") (pintype "bidirectional"))
      (node (ref "RN4") (pin "8") (pinfunction "2_8") (pintype "passive"))
      (node (ref "RN8") (pin "1") (pinfunction "1_1") (pintype "passive"))
    )
    (net (code "25") (name "1G1") (class "Default")
      (node (ref "J4") (pin "G1") (pinfunction "G1_G1") (pintype "bidirectional"))
      (node (ref "RN10") (pin "5") (pinfunction "2_5") (pintype "passive"))
      (node (ref "RN14") (pin "4") (pinfunction "1_4") (pintype "passive"))
    )
    (net (code "26") (name "1G2") (class "Default")
      (node (ref "J4") (pin "G2") (pinfunction "G2_G2") (pintype "bidirectional"))
      (node (ref "RN10") (pin "6") (pinfunction "2_6") (pintype "passive"))
      (node (ref "RN14") (pin "3") (pinfunction "1_3") (pintype "passive"))
    )
    (net (code "27") (name "1G3") (class "Default")
      (node (ref "J4") (pin "G3") (pinfunction "G3_G3") (pintype "bidirectional"))
      (node (ref "RN10") (pin "7") (pinfunction "2_7") (pintype "passive"))
      (node (ref "RN14") (pin "2") (pinfunction "1_2") (pintype "passive"))
    )
    (net (code "28") (name "1G6") (class "Default")
      (node (ref "J4") (pin "G6") (pinfunction "G6_G6") (pintype "bidirectional"))
      (node (ref "RN10") (pin "8") (pinfunction "2_8") (pintype "passive"))
      (node (ref "RN14") (pin "1") (pinfunction "1_1") (pintype "passive"))
    )
    (net (code "29") (name "1H1") (class "Default")
      (node (ref "J4") (pin "H1") (pinfunction "H1_H1") (pintype "bidirectional"))
      (node (ref "RN12") (pin "5") (pinfunction "2_5") (pintype "passive"))
      (node (ref "RN16") (pin "4") (pinfunction "1_4") (pintype "passive"))
    )
    (net (code "30") (name "1H2") (class "Default")
      (node (ref "J4") (pin "H2") (pinfunction "H2_H2") (pintype "bidirectional"))
      (node (ref "RN12") (pin "6") (pinfunction "2_6") (pintype "passive"))
      (node (ref "RN16") (pin "3") (pinfunction "1_3") (pintype "passive"))
    )
    (net (code "31") (name "1H3") (class "Default")
      (node (ref "J4") (pin "H3") (pinfunction "H3_H3") (pintype "bidirectional"))
      (node (ref "RN12") (pin "7") (pinfunction "2_7") (pintype "passive"))
      (node (ref "RN16") (pin "2") (pinfunction "1_2") (pintype "passive"))
    )
    (net (code "32") (name "1H6") (class "Default")
      (node (ref "J4") (pin "H6") (pinfunction "H6_H6") (pintype "bidirectional"))
      (node (ref "RN12") (pin "8") (pinfunction "2_8") (pintype "passive"))
      (node (ref "RN16") (pin "1") (pinfunction "1_1") (pintype "passive"))
    )
    (net (code "33") (name "2A1") (class "Default")
      (node (ref "J5") (pin "A1") (pinfunction "A1_A1") (pintype "bidirectional"))
      (node (ref "RN17") (pin "5") (pinfunction "2_5") (pintype "passive"))
      (node (ref "RN21") (pin "4") (pinfunction "1_4") (pintype "passive"))
    )
    (net (code "34") (name "2A2") (class "Default")
      (node (ref "J5") (pin "A2") (pinfunction "A2_A2") (pintype "bidirectional"))
      (node (ref "RN17") (pin "6") (pinfunction "2_6") (pintype "passive"))
      (node (ref "RN21") (pin "3") (pinfunction "1_3") (pintype "passive"))
    )
    (net (code "35") (name "2A3") (class "Default")
      (node (ref "J5") (pin "A3") (pinfunction "A3_A3") (pintype "bidirectional"))
      (node (ref "RN17") (pin "7") (pinfunction "2_7") (pintype "passive"))
      (node (ref "RN21") (pin "2") (pinfunction "1_2") (pintype "passive"))
    )
    (net (code "36") (name "2A6") (class "Default")
      (node (ref "J5") (pin "A6") (pinfunction "A6_A6") (pintype "bidirectional"))
      (node (ref "RN17") (pin "8") (pinfunction "2_8") (pintype "passive"))
      (node (ref "RN21") (pin "1") (pinfunction "1_1") (pintype "passive"))
    )
    (net (code "37") (name "2B1") (class "Default")
      (node (ref "J5") (pin "B1") (pinfunction "B1_B1") (pintype "bidirectional"))
      (node (ref "RN19") (pin "5") (pinfunction "2_5") (pintype "passive"))
      (node (ref "RN23") (pin "4") (pinfunction "1_4") (pintype "passive"))
    )
    (net (code "38") (name "2B2") (class "Default")
      (node (ref "J5") (pin "B2") (pinfunction "B2_B2") (pintype "bidirectional"))
      (node (ref "RN19") (pin "6") (pinfunction "2_6") (pintype "passive"))
      (node (ref "RN23") (pin "3") (pinfunction "1_3") (pintype "passive"))
    )
    (net (code "39") (name "2B3") (class "Default")
      (node (ref "J5") (pin "B3") (pinfunction "B3_B3") (pintype "bidirectional"))
      (node (ref "RN19") (pin "7") (pinfunction "2_7") (pintype "passive"))
      (node (ref "RN23") (pin "2") (pinfunction "1_2") (pintype "passive"))
    )
    (net (code "40") (name "2B6") (class "Default")
      (node (ref "J5") (pin "B6") (pinfunction "B6_B6") (pintype "bidirectional"))
      (node (ref "RN19") (pin "8") (pinfunction "2_8") (pintype "passive"))
      (node (ref "RN23") (pin "1") (pinfunction "1_1") (pintype "passive"))
    )
    (net (code "41") (name "2C1") (class "Default")
      (node (ref "J5") (pin "C1") (pinfunction "C1_C1") (pintype "bidirectional"))
      (node (ref "RN25") (pin "5") (pinfunction "2_5") (pintype "passive"))
      (node (ref "RN29") (pin "4") (pinfunction "1_4") (pintype "passive"))
    )
    (net (code "42") (name "2C2") (class "Default")
      (node (ref "J5") (pin "C2") (pinfunction "C2_C2") (pintype "bidirectional"))
      (node (ref "RN25") (pin "6") (pinfunction "2_6") (pintype "passive"))
      (node (ref "RN29") (pin "3") (pinfunction "1_3") (pintype "passive"))
    )
    (net (code "43") (name "2C3") (class "Default")
      (node (ref "J5") (pin "C3") (pinfunction "C3_C3") (pintype "bidirectional"))
      (node (ref "RN25") (pin "7") (pinfunction "2_7") (pintype "passive"))
      (node (ref "RN29") (pin "2") (pinfunction "1_2") (pintype "passive"))
    )
    (net (code "44") (name "2C6") (class "Default")
      (node (ref "J5") (pin "C6") (pinfunction "C6_C6") (pintype "bidirectional"))
      (node (ref "RN25") (pin "8") (pinfunction "2_8") (pintype "passive"))
      (node (ref "RN29") (pin "1") (pinfunction "1_1") (pintype "passive"))
    )
    (net (code "45") (name "2D1") (class "Default")
      (node (ref "J5") (pin "D1") (pinfunction "D1_D1") (pintype "bidirectional"))
      (node (ref "RN27") (pin "5") (pinfunction "2_5") (pintype "passive"))
      (node (ref "RN31") (pin "4") (pinfunction "1_4") (pintype "passive"))
    )
    (net (code "46") (name "2D2") (class "Default")
      (node (ref "J5") (pin "D2") (pinfunction "D2_D2") (pintype "bidirectional"))
      (node (ref "RN27") (pin "6") (pinfunction "2_6") (pintype "passive"))
      (node (ref "RN31") (pin "3") (pinfunction "1_3") (pintype "passive"))
    )
    (net (code "47") (name "2D3") (class "Default")
      (node (ref "J5") (pin "D3") (pinfunction "D3_D3") (pintype "bidirectional"))
      (node (ref "RN27") (pin "7") (pinfunction "2_7") (pintype "passive"))
      (node (ref "RN31") (pin "2") (pinfunction "1_2") (pintype "passive"))
    )
    (net (code "48") (name "2D6") (class "Default")
      (node (ref "J5") (pin "D6") (pinfunction "D6_D6") (pintype "bidirectional"))
      (node (ref "RN27") (pin "8") (pinfunction "2_8") (pintype "passive"))
      (node (ref "RN31") (pin "1") (pinfunction "1_1") (pintype "passive"))
    )
    (net (code "49") (name "2E1") (class "Default")
      (node (ref "J5") (pin "E1") (pinfunction "E1_E1") (pintype "bidirectional"))
      (node (ref "RN18") (pin "5") (pinfunction "2_5") (pintype "passive"))
      (node (ref "RN22") (pin "4") (pinfunction "1_4") (pintype "passive"))
    )
    (net (code "50") (name "2E2") (class "Default")
      (node (ref "J5") (pin "E2") (pinfunction "E2_E2") (pintype "bidirectional"))
      (node (ref "RN18") (pin "6") (pinfunction "2_6") (pintype "passive"))
      (node (ref "RN22") (pin "3") (pinfunction "1_3") (pintype "passive"))
    )
    (net (code "51") (name "2E3") (class "Default")
      (node (ref "J5") (pin "E3") (pinfunction "E3_E3") (pintype "bidirectional"))
      (node (ref "RN18") (pin "7") (pinfunction "2_7") (pintype "passive"))
      (node (ref "RN22") (pin "2") (pinfunction "1_2") (pintype "passive"))
    )
    (net (code "52") (name "2E6") (class "Default")
      (node (ref "J5") (pin "E6") (pinfunction "E6_E6") (pintype "bidirectional"))
      (node (ref "RN18") (pin "8") (pinfunction "2_8") (pintype "passive"))
      (node (ref "RN22") (pin "1") (pinfunction "1_1") (pintype "passive"))
    )
    (net (code "53") (name "2F1") (class "Default")
      (node (ref "J5") (pin "F1") (pinfunction "F1_F1") (pintype "bidirectional"))
      (node (ref "RN20") (pin "5") (pinfunction "2_5") (pintype "passive"))
      (node (ref "RN24") (pin "4") (pinfunction "1_4") (pintype "passive"))
    )
    (net (code "54") (name "2F2") (class "Default")
      (node (ref "J5") (pin "F2") (pinfunction "F2_F2") (pintype "bidirectional"))
      (node (ref "RN20") (pin "6") (pinfunction "2_6") (pintype "passive"))
      (node (ref "RN24") (pin "3") (pinfunction "1_3") (pintype "passive"))
    )
    (net (code "55") (name "2F3") (class "Default")
      (node (ref "J5") (pin "F3") (pinfunction "F3_F3") (pintype "bidirectional"))
      (node (ref "RN20") (pin "7") (pinfunction "2_7") (pintype "passive"))
      (node (ref "RN24") (pin "2") (pinfunction "1_2") (pintype "passive"))
    )
    (net (code "56") (name "2F6") (class "Default")
      (node (ref "J5") (pin "F6") (pinfunction "F6_F6") (pintype "bidirectional"))
      (node (ref "RN20") (pin "8") (pinfunction "2_8") (pintype "passive"))
      (node (ref "RN24") (pin "1") (pinfunction "1_1") (pintype "passive"))
    )
    (net (code "57") (name "2G1") (class "Default")
      (node (ref "J5") (pin "G1") (pinfunction "G1_G1") (pintype "bidirectional"))
      (node (ref "RN26") (pin "5") (pinfunction "2_5") (pintype "passive"))
      (node (ref "RN30") (pin "4") (pinfunction "1_4") (pintype "passive"))
    )
    (net (code "58") (name "2G2") (class "Default")
      (node (ref "J5") (pin "G2") (pinfunction "G2_G2") (pintype "bidirectional"))
      (node (ref "RN26") (pin "6") (pinfunction "2_6") (pintype "passive"))
      (node (ref "RN30") (pin "3") (pinfunction "1_3") (pintype "passive"))
    )
    (net (code "59") (name "2G3") (class "Default")
      (node (ref "J5") (pin "G3") (pinfunction "G3_G3") (pintype "bidirectional"))
      (node (ref "RN26") (pin "7") (pinfunction "2_7") (pintype "passive"))
      (node (ref "RN30") (pin "2") (pinfunction "1_2") (pintype "passive"))
    )
    (net (code "60") (name "2G6") (class "Default")
      (node (ref "J5") (pin "G6") (pinfunction "G6_G6") (pintype "bidirectional"))
      (node (ref "RN26") (pin "8") (pinfunction "2_8") (pintype "passive"))
      (node (ref "RN30") (pin "1") (pinfunction "1_1") (pintype "passive"))
    )
    (net (code "61") (name "2H1") (class "Default")
      (node (ref "J5") (pin "H1") (pinfunction "H1_H1") (pintype "bidirectional"))
      (node (ref "RN28") (pin "5") (pinfunction "2_5") (pintype "passive"))
      (node (ref "RN32") (pin "4") (pinfunction "1_4") (pintype "passive"))
    )
    (net (code "62") (name "2H2") (class "Default")
      (node (ref "J5") (pin "H2") (pinfunction "H2_H2") (pintype "bidirectional"))
      (node (ref "RN28") (pin "6") (pinfunction "2_6") (pintype "passive"))
      (node (ref "RN32") (pin "3") (pinfunction "1_3") (pintype "passive"))
    )
    (net (code "63") (name "2H3") (class "Default")
      (node (ref "J5") (pin "H3") (pinfunction "H3_H3") (pintype "bidirectional"))
      (node (ref "RN28") (pin "7") (pinfunction "2_7") (pintype "passive"))
      (node (ref "RN32") (pin "2") (pinfunction "1_2") (pintype "passive"))
    )
    (net (code "64") (name "2H6") (class "Default")
      (node (ref "J5") (pin "H6") (pinfunction "H6_H6") (pintype "bidirectional"))
      (node (ref "RN28") (pin "8") (pinfunction "2_8") (pintype "passive"))
      (node (ref "RN32") (pin "1") (pinfunction "1_1") (pintype "passive"))
    )
    (net (code "65") (name "3A1") (class "Default")
      (node (ref "J6") (pin "A1") (pinfunction "A1_A1") (pintype "bidirectional"))
      (node (ref "RN33") (pin "5") (pinfunction "2_5") (pintype "passive"))
      (node (ref "RN44") (pin "4") (pinfunction "1_4") (pintype "passive"))
    )
    (net (code "66") (name "3A2") (class "Default")
      (node (ref "J6") (pin "A2") (pinfunction "A2_A2") (pintype "bidirectional"))
      (node (ref "RN33") (pin "6") (pinfunction "2_6") (pintype "passive"))
      (node (ref "RN44") (pin "3") (pinfunction "1_3") (pintype "passive"))
    )
    (net (code "67") (name "3A3") (class "Default")
      (node (ref "J6") (pin "A3") (pinfunction "A3_A3") (pintype "bidirectional"))
      (node (ref "RN33") (pin "7") (pinfunction "2_7") (pintype "passive"))
      (node (ref "RN44") (pin "2") (pinfunction "1_2") (pintype "passive"))
    )
    (net (code "68") (name "3A6") (class "Default")
      (node (ref "J6") (pin "A6") (pinfunction "A6_A6") (pintype "bidirectional"))
      (node (ref "RN33") (pin "8") (pinfunction "2_8") (pintype "passive"))
      (node (ref "RN44") (pin "1") (pinfunction "1_1") (pintype "passive"))
    )
    (net (code "69") (name "3B1") (class "Default")
      (node (ref "J6") (pin "B1") (pinfunction "B1_B1") (pintype "bidirectional"))
      (node (ref "RN35") (pin "5") (pinfunction "2_5") (pintype "passive"))
      (node (ref "RN42") (pin "4") (pinfunction "1_4") (pintype "passive"))
    )
    (net (code "70") (name "3B2") (class "Default")
      (node (ref "J6") (pin "B2") (pinfunction "B2_B2") (pintype "bidirectional"))
      (node (ref "RN35") (pin "6") (pinfunction "2_6") (pintype "passive"))
      (node (ref "RN42") (pin "3") (pinfunction "1_3") (pintype "passive"))
    )
    (net (code "71") (name "3B3") (class "Default")
      (node (ref "J6") (pin "B3") (pinfunction "B3_B3") (pintype "bidirectional"))
      (node (ref "RN35") (pin "7") (pinfunction "2_7") (pintype "passive"))
      (node (ref "RN42") (pin "2") (pinfunction "1_2") (pintype "passive"))
    )
    (net (code "72") (name "3B6") (class "Default")
      (node (ref "J6") (pin "B6") (pinfunction "B6_B6") (pintype "bidirectional"))
      (node (ref "RN35") (pin "8") (pinfunction "2_8") (pintype "passive"))
      (node (ref "RN42") (pin "1") (pinfunction "1_1") (pintype "passive"))
    )
    (net (code "73") (name "3C1") (class "Default")
      (node (ref "J6") (pin "C1") (pinfunction "C1_C1") (pintype "bidirectional"))
      (node (ref "RN37") (pin "5") (pinfunction "2_5") (pintype "passive"))
      (node (ref "RN48") (pin "4") (pinfunction "1_4") (pintype "passive"))
    )
    (net (code "74") (name "3C2") (class "Default")
      (node (ref "J6") (pin "C2") (pinfunction "C2_C2") (pintype "bidirectional"))
      (node (ref "RN37") (pin "6") (pinfunction "2_6") (pintype "passive"))
      (node (ref "RN48") (pin "3") (pinfunction "1_3") (pintype "passive"))
    )
    (net (code "75") (name "3C3") (class "Default")
      (node (ref "J6") (pin "C3") (pinfunction "C3_C3") (pintype "bidirectional"))
      (node (ref "RN37") (pin "7") (pinfunction "2_7") (pintype "passive"))
      (node (ref "RN48") (pin "2") (pinfunction "1_2") (pintype "passive"))
    )
    (net (code "76") (name "3C6") (class "Default")
      (node (ref "J6") (pin "C6") (pinfunction "C6_C6") (pintype "bidirectional"))
      (node (ref "RN37") (pin "8") (pinfunction "2_8") (pintype "passive"))
      (node (ref "RN48") (pin "1") (pinfunction "1_1") (pintype "passive"))
    )
    (net (code "77") (name "3D1") (class "Default")
      (node (ref "J6") (pin "D1") (pinfunction "D1_D1") (pintype "bidirectional"))
      (node (ref "RN39") (pin "5") (pinfunction "2_5") (pintype "passive"))
      (node (ref "RN46") (pin "4") (pinfunction "1_4") (pintype "passive"))
    )
    (net (code "78") (name "3D2") (class "Default")
      (node (ref "J6") (pin "D2") (pinfunction "D2_D2") (pintype "bidirectional"))
      (node (ref "RN39") (pin "6") (pinfunction "2_6") (pintype "passive"))
      (node (ref "RN46") (pin "3") (pinfunction "1_3") (pintype "passive"))
    )
    (net (code "79") (name "3D3") (class "Default")
      (node (ref "J6") (pin "D3") (pinfunction "D3_D3") (pintype "bidirectional"))
      (node (ref "RN39") (pin "7") (pinfunction "2_7") (pintype "passive"))
      (node (ref "RN46") (pin "2") (pinfunction "1_2") (pintype "passive"))
    )
    (net (code "80") (name "3D6") (class "Default")
      (node (ref "J6") (pin "D6") (pinfunction "D6_D6") (pintype "bidirectional"))
      (node (ref "RN39") (pin "8") (pinfunction "2_8") (pintype "passive"))
      (node (ref "RN46") (pin "1") (pinfunction "1_1") (pintype "passive"))
    )
    (net (code "81") (name "3E1") (class "Default")
      (node (ref "J6") (pin "E1") (pinfunction "E1_E1") (pintype "bidirectional"))
      (node (ref "RN34") (pin "5") (pinfunction "2_5") (pintype "passive"))
      (node (ref "RN43") (pin "4") (pinfunction "1_4") (pintype "passive"))
    )
    (net (code "82") (name "3E2") (class "Default")
      (node (ref "J6") (pin "E2") (pinfunction "E2_E2") (pintype "bidirectional"))
      (node (ref "RN34") (pin "6") (pinfunction "2_6") (pintype "passive"))
      (node (ref "RN43") (pin "3") (pinfunction "1_3") (pintype "passive"))
    )
    (net (code "83") (name "3E3") (class "Default")
      (node (ref "J6") (pin "E3") (pinfunction "E3_E3") (pintype "bidirectional"))
      (node (ref "RN34") (pin "7") (pinfunction "2_7") (pintype "passive"))
      (node (ref "RN43") (pin "2") (pinfunction "1_2") (pintype "passive"))
    )
    (net (code "84") (name "3E6") (class "Default")
      (node (ref "J6") (pin "E6") (pinfunction "E6_E6") (pintype "bidirectional"))
      (node (ref "RN34") (pin "8") (pinfunction "2_8") (pintype "passive"))
      (node (ref "RN43") (pin "1") (pinfunction "1_1") (pintype "passive"))
    )
    (net (code "85") (name "3F1") (class "Default")
      (node (ref "J6") (pin "F1") (pinfunction "F1_F1") (pintype "bidirectional"))
      (node (ref "RN36") (pin "5") (pinfunction "2_5") (pintype "passive"))
      (node (ref "RN41") (pin "4") (pinfunction "1_4") (pintype "passive"))
    )
    (net (code "86") (name "3F2") (class "Default")
      (node (ref "J6") (pin "F2") (pinfunction "F2_F2") (pintype "bidirectional"))
      (node (ref "RN36") (pin "6") (pinfunction "2_6") (pintype "passive"))
      (node (ref "RN41") (pin "3") (pinfunction "1_3") (pintype "passive"))
    )
    (net (code "87") (name "3F3") (class "Default")
      (node (ref "J6") (pin "F3") (pinfunction "F3_F3") (pintype "bidirectional"))
      (node (ref "RN36") (pin "7") (pinfunction "2_7") (pintype "passive"))
      (node (ref "RN41") (pin "2") (pinfunction "1_2") (pintype "passive"))
    )
    (net (code "88") (name "3F6") (class "Default")
      (node (ref "J6") (pin "F6") (pinfunction "F6_F6") (pintype "bidirectional"))
      (node (ref "RN36") (pin "8") (pinfunction "2_8") (pintype "passive"))
      (node (ref "RN41") (pin "1") (pinfunction "1_1") (pintype "passive"))
    )
    (net (code "89") (name "3G1") (class "Default")
      (node (ref "J6") (pin "G1") (pinfunction "G1_G1") (pintype "bidirectional"))
      (node (ref "RN38") (pin "5") (pinfunction "2_5") (pintype "passive"))
      (node (ref "RN47") (pin "4") (pinfunction "1_4") (pintype "passive"))
    )
    (net (code "90") (name "3G2") (class "Default")
      (node (ref "J6") (pin "G2") (pinfunction "G2_G2") (pintype "bidirectional"))
      (node (ref "RN38") (pin "6") (pinfunction "2_6") (pintype "passive"))
      (node (ref "RN47") (pin "3") (pinfunction "1_3") (pintype "passive"))
    )
    (net (code "91") (name "3G3") (class "Default")
      (node (ref "J6") (pin "G3") (pinfunction "G3_G3") (pintype "bidirectional"))
      (node (ref "RN38") (pin "7") (pinfunction "2_7") (pintype "passive"))
      (node (ref "RN47") (pin "2") (pinfunction "1_2") (pintype "passive"))
    )
    (net (code "92") (name "3G6") (class "Default")
      (node (ref "J6") (pin "G6") (pinfunction "G6_G6") (pintype "bidirectional"))
      (node (ref "RN38") (pin "8") (pinfunction "2_8") (pintype "passive"))
      (node (ref "RN47") (pin "1") (pinfunction "1_1") (pintype "passive"))
    )
    (net (code "93") (name "3H1") (class "Default")
      (node (ref "J6") (pin "H1") (pinfunction "H1_H1") (pintype "bidirectional"))
      (node (ref "RN40") (pin "5") (pinfunction "2_5") (pintype "passive"))
      (node (ref "RN45") (pin "4") (pinfunction "1_4") (pintype "passive"))
    )
    (net (code "94") (name "3H2") (class "Default")
      (node (ref "J6") (pin "H2") (pinfunction "H2_H2") (pintype "bidirectional"))
      (node (ref "RN40") (pin "6") (pinfunction "2_6") (pintype "passive"))
      (node (ref "RN45") (pin "3") (pinfunction "1_3") (pintype "passive"))
    )
    (net (code "95") (name "3H3") (class "Default")
      (node (ref "J6") (pin "H3") (pinfunction "H3_H3") (pintype "bidirectional"))
      (node (ref "RN40") (pin "7") (pinfunction "2_7") (pintype "passive"))
      (node (ref "RN45") (pin "2") (pinfunction "1_2") (pintype "passive"))
    )
    (net (code "96") (name "3H6") (class "Default")
      (node (ref "J6") (pin "H6") (pinfunction "H6_H6") (pintype "bidirectional"))
      (node (ref "RN40") (pin "8") (pinfunction "2_8") (pintype "passive"))
      (node (ref "RN45") (pin "1") (pinfunction "1_1") (pintype "passive"))
    )
    (net (code "97") (name "GND") (class "Default")
      (node (ref "C1") (pin "2") (pinfunction "2_2") (pintype "passive"))
      (node (ref "C2") (pin "2") (pinfunction "2_2") (pintype "passive"))
      (node (ref "C3") (pin "2") (pinfunction "2_2") (pintype "passive"))
      (node (ref "C4") (pin "2") (pinfunction "2_2") (pintype "passive"))
      (node (ref "C5") (pin "2") (pinfunction "2_2") (pintype "passive"))
      (node (ref "C6") (pin "2") (pinfunction "2_2") (pintype "passive"))
      (node (ref "C7") (pin "-") (pinfunction "-_-") (pintype "passive"))
      (node (ref "C8") (pin "-") (pinfunction "-_-") (pintype "passive"))
      (node (ref "C9") (pin "-") (pinfunction "-_-") (pintype "passive"))
      (node (ref "IC1") (pin "10") (pinfunction "VSS_10") (pintype "power_in"))
      (node (ref "IC2") (pin "10") (pinfunction "VSS_10") (pintype "power_in"))
      (node (ref "IC3") (pin "10") (pinfunction "VSS_10") (pintype "power_in"))
      (node (ref "IC4") (pin "10") (pinfunction "VSS_10") (pintype "power_in"))
      (node (ref "IC5") (pin "10") (pinfunction "VSS_10") (pintype "power_in"))
      (node (ref "IC6") (pin "10") (pinfunction "VSS_10") (pintype "power_in"))
      (node (ref "J1") (pin "4") (pinfunction "4_4") (pintype "passive"))
      (node (ref "J2") (pin "4") (pinfunction "4_4") (pintype "passive"))
      (node (ref "J4") (pin "A7") (pinfunction "A7_A7") (pintype "bidirectional"))
      (node (ref "J4") (pin "A8") (pinfunction "A8_A8") (pintype "bidirectional"))
      (node (ref "J4") (pin "B7") (pinfunction "B7_B7") (pintype "bidirectional"))
      (node (ref "J4") (pin "B8") (pinfunction "B8_B8") (pintype "bidirectional"))
      (node (ref "J4") (pin "C7") (pinfunction "C7_C7") (pintype "bidirectional"))
      (node (ref "J4") (pin "C8") (pinfunction "C8_C8") (pintype "bidirectional"))
      (node (ref "J4") (pin "D7") (pinfunction "D7_D7") (pintype "bidirectional"))
      (node (ref "J4") (pin "D8") (pinfunction "D8_D8") (pintype "bidirectional"))
      (node (ref "J4") (pin "E7") (pinfunction "E7_E7") (pintype "bidirectional"))
      (node (ref "J4") (pin "E8") (pinfunction "E8_E8") (pintype "bidirectional"))
      (node (ref "J4") (pin "F7") (pinfunction "F7_F7") (pintype "bidirectional"))
      (node (ref "J4") (pin "F8") (pinfunction "F8_F8") (pintype "bidirectional"))
      (node (ref "J4") (pin "G7") (pinfunction "G7_G7") (pintype "bidirectional"))
      (node (ref "J4") (pin "G8") (pinfunction "G8_G8") (pintype "bidirectional"))
      (node (ref "J4") (pin "GND0") (pinfunction "GND0_GND0") (pintype "power_in"))
      (node (ref "J4") (pin "GND1") (pinfunction "GND1_GND1") (pintype "power_in"))
      (node (ref "J4") (pin "GND2") (pinfunction "GND2_GND2") (pintype "power_in"))
      (node (ref "J4") (pin "GND3") (pinfunction "GND3_GND3") (pintype "power_in"))
      (node (ref "J4") (pin "GND4") (pinfunction "GND4_GND4") (pintype "power_in"))
      (node (ref "J4") (pin "GND5") (pinfunction "GND5_GND5") (pintype "power_in"))
      (node (ref "J4") (pin "H7") (pinfunction "H7_H7") (pintype "bidirectional"))
      (node (ref "J4") (pin "H8") (pinfunction "H8_H8") (pintype "bidirectional"))
      (node (ref "J5") (pin "A7") (pinfunction "A7_A7") (pintype "bidirectional"))
      (node (ref "J5") (pin "A8") (pinfunction "A8_A8") (pintype "bidirectional"))
      (node (ref "J5") (pin "B7") (pinfunction "B7_B7") (pintype "bidirectional"))
      (node (ref "J5") (pin "B8") (pinfunction "B8_B8") (pintype "bidirectional"))
      (node (ref "J5") (pin "C7") (pinfunction "C7_C7") (pintype "bidirectional"))
      (node (ref "J5") (pin "C8") (pinfunction "C8_C8") (pintype "bidirectional"))
      (node (ref "J5") (pin "D7") (pinfunction "D7_D7") (pintype "bidirectional"))
      (node (ref "J5") (pin "D8") (pinfunction "D8_D8") (pintype "bidirectional"))
      (node (ref "J5") (pin "E7") (pinfunction "E7_E7") (pintype "bidirectional"))
      (node (ref "J5") (pin "E8") (pinfunction "E8_E8") (pintype "bidirectional"))
      (node (ref "J5") (pin "F7") (pinfunction "F7_F7") (pintype "bidirectional"))
      (node (ref "J5") (pin "F8") (pinfunction "F8_F8") (pintype "bidirectional"))
      (node (ref "J5") (pin "G7") (pinfunction "G7_G7") (pintype "bidirectional"))
      (node (ref "J5") (pin "G8") (pinfunction "G8_G8") (pintype "bidirectional"))
      (node (ref "J5") (pin "GND0") (pinfunction "GND0_GND0") (pintype "power_in"))
      (node (ref "J5") (pin "GND1") (pinfunction "GND1_GND1") (pintype "power_in"))
      (node (ref "J5") (pin "GND2") (pinfunction "GND2_GND2") (pintype "power_in"))
      (node (ref "J5") (pin "GND3") (pinfunction "GND3_GND3") (pintype "power_in"))
      (node (ref "J5") (pin "GND4") (pinfunction "GND4_GND4") (pintype "power_in"))
      (node (ref "J5") (pin "GND5") (pinfunction "GND5_GND5") (pintype "power_in"))
      (node (ref "J5") (pin "H7") (pinfunction "H7_H7") (pintype "bidirectional"))
      (node (ref "J5") (pin "H8") (pinfunction "H8_H8") (pintype "bidirectional"))
      (node (ref "J6") (pin "A7") (pinfunction "A7_A7") (pintype "bidirectional"))
      (node (ref "J6") (pin "A8") (pinfunction "A8_A8") (pintype "bidirectional"))
      (node (ref "J6") (pin "B7") (pinfunction "B7_B7") (pintype "bidirectional"))
      (node (ref "J6") (pin "B8") (pinfunction "B8_B8") (pintype "bidirectional"))
      (node (ref "J6") (pin "C7") (pinfunction "C7_C7") (pintype "bidirectional"))
      (node (ref "J6") (pin "C8") (pinfunction "C8_C8") (pintype "bidirectional"))
      (node (ref "J6") (pin "D7") (pinfunction "D7_D7") (pintype "bidirectional"))
      (node (ref "J6") (pin "D8") (pinfunction "D8_D8") (pintype "bidirectional"))
      (node (ref "J6") (pin "E7") (pinfunction "E7_E7") (pintype "bidirectional"))
      (node (ref "J6") (pin "E8") (pinfunction "E8_E8") (pintype "bidirectional"))
      (node (ref "J6") (pin "F7") (pinfunction "F7_F7") (pintype "bidirectional"))
      (node (ref "J6") (pin "F8") (pinfunction "F8_F8") (pintype "bidirectional"))
      (node (ref "J6") (pin "G7") (pinfunction "G7_G7") (pintype "bidirectional"))
      (node (ref "J6") (pin "G8") (pinfunction "G8_G8") (pintype "bidirectional"))
      (node (ref "J6") (pin "GND0") (pinfunction "GND0_GND0") (pintype "power_in"))
      (node (ref "J6") (pin "GND1") (pinfunction "GND1_GND1") (pintype "power_in"))
      (node (ref "J6") (pin "GND2") (pinfunction "GND2_GND2") (pintype "power_in"))
      (node (ref "J6") (pin "GND3") (pinfunction "GND3_GND3") (pintype "power_in"))
      (node (ref "J6") (pin "GND4") (pinfunction "GND4_GND4") (pintype "power_in"))
      (node (ref "J6") (pin "GND5") (pinfunction "GND5_GND5") (pintype "power_in"))
      (node (ref "J6") (pin "H7") (pinfunction "H7_H7") (pintype "bidirectional"))
      (node (ref "J6") (pin "H8") (pinfunction "H8_H8") (pintype "bidirectional"))
      (node (ref "LED1") (pin "C") (pinfunction "C_C") (pintype "passive"))
      (node (ref "LED2") (pin "C") (pinfunction "C_C") (pintype "passive"))
      (node (ref "RN49") (pin "1") (pinfunction "1_1") (pintype "passive"))
      (node (ref "RN49") (pin "2") (pinfunction "1_2") (pintype "passive"))
      (node (ref "RN49") (pin "3") (pinfunction "1_3") (pintype "passive"))
      (node (ref "RN49") (pin "4") (pinfunction "1_4") (pintype "passive"))
      (node (ref "RN50") (pin "1") (pinfunction "1_1") (pintype "passive"))
      (node (ref "RN50") (pin "2") (pinfunction "1_2") (pintype "passive"))
      (node (ref "RN50") (pin "3") (pinfunction "1_3") (pintype "passive"))
      (node (ref "RN50") (pin "4") (pinfunction "1_4") (pintype "passive"))
      (node (ref "RN51") (pin "1") (pinfunction "1_1") (pintype "passive"))
      (node (ref "RN51") (pin "2") (pinfunction "1_2") (pintype "passive"))
      (node (ref "RN51") (pin "3") (pinfunction "1_3") (pintype "passive"))
      (node (ref "RN51") (pin "4") (pinfunction "1_4") (pintype "passive"))
      (node (ref "RN52") (pin "1") (pinfunction "1_1") (pintype "passive"))
      (node (ref "RN52") (pin "2") (pinfunction "1_2") (pintype "passive"))
      (node (ref "RN52") (pin "3") (pinfunction "1_3") (pintype "passive"))
      (node (ref "RN52") (pin "4") (pinfunction "1_4") (pintype "passive"))
      (node (ref "RN53") (pin "1") (pinfunction "1_1") (pintype "passive"))
      (node (ref "RN53") (pin "2") (pinfunction "1_2") (pintype "passive"))
      (node (ref "RN53") (pin "3") (pinfunction "1_3") (pintype "passive"))
      (node (ref "RN53") (pin "4") (pinfunction "1_4") (pintype "passive"))
      (node (ref "RN54") (pin "1") (pinfunction "1_1") (pintype "passive"))
      (node (ref "RN54") (pin "2") (pinfunction "1_2") (pintype "passive"))
      (node (ref "RN54") (pin "3") (pinfunction "1_3") (pintype "passive"))
      (node (ref "RN54") (pin "4") (pinfunction "1_4") (pintype "passive"))
    )
    (net (code "98") (name "GPA0-1") (class "Default")
      (node (ref "IC1") (pin "21") (pinfunction "GPA0_21") (pintype "bidirectional"))
      (node (ref "RN1") (pin "4") (pinfunction "1_4") (pintype "passive"))
    )
    (net (code "99") (name "GPA0-2") (class "Default")
      (node (ref "IC2") (pin "21") (pinfunction "GPA0_21") (pintype "bidirectional"))
      (node (ref "RN9") (pin "4") (pinfunction "1_4") (pintype "passive"))
    )
    (net (code "100") (name "GPA0-3") (class "Default")
      (node (ref "IC3") (pin "21") (pinfunction "GPA0_21") (pintype "bidirectional"))
      (node (ref "RN17") (pin "4") (pinfunction "1_4") (pintype "passive"))
    )
    (net (code "101") (name "GPA0-4") (class "Default")
      (node (ref "IC4") (pin "21") (pinfunction "GPA0_21") (pintype "bidirectional"))
      (node (ref "RN25") (pin "4") (pinfunction "1_4") (pintype "passive"))
    )
    (net (code "102") (name "GPA0-5") (class "Default")
      (node (ref "IC5") (pin "21") (pinfunction "GPA0_21") (pintype "bidirectional"))
      (node (ref "RN33") (pin "4") (pinfunction "1_4") (pintype "passive"))
    )
    (net (code "103") (name "GPA0-6") (class "Default")
      (node (ref "IC6") (pin "21") (pinfunction "GPA0_21") (pintype "bidirectional"))
      (node (ref "RN37") (pin "4") (pinfunction "1_4") (pintype "passive"))
    )
    (net (code "104") (name "GPA1-1") (class "Default")
      (node (ref "IC1") (pin "22") (pinfunction "GPA1_22") (pintype "bidirectional"))
      (node (ref "RN1") (pin "3") (pinfunction "1_3") (pintype "passive"))
    )
    (net (code "105") (name "GPA1-2") (class "Default")
      (node (ref "IC2") (pin "22") (pinfunction "GPA1_22") (pintype "bidirectional"))
      (node (ref "RN9") (pin "3") (pinfunction "1_3") (pintype "passive"))
    )
    (net (code "106") (name "GPA1-3") (class "Default")
      (node (ref "IC3") (pin "22") (pinfunction "GPA1_22") (pintype "bidirectional"))
      (node (ref "RN17") (pin "3") (pinfunction "1_3") (pintype "passive"))
    )
    (net (code "107") (name "GPA1-4") (class "Default")
      (node (ref "IC4") (pin "22") (pinfunction "GPA1_22") (pintype "bidirectional"))
      (node (ref "RN25") (pin "3") (pinfunction "1_3") (pintype "passive"))
    )
    (net (code "108") (name "GPA1-5") (class "Default")
      (node (ref "IC5") (pin "22") (pinfunction "GPA1_22") (pintype "bidirectional"))
      (node (ref "RN33") (pin "3") (pinfunction "1_3") (pintype "passive"))
    )
    (net (code "109") (name "GPA1-6") (class "Default")
      (node (ref "IC6") (pin "22") (pinfunction "GPA1_22") (pintype "bidirectional"))
      (node (ref "RN37") (pin "3") (pinfunction "1_3") (pintype "passive"))
    )
    (net (code "110") (name "GPA2-1") (class "Default")
      (node (ref "IC1") (pin "23") (pinfunction "GPA2_23") (pintype "bidirectional"))
      (node (ref "RN1") (pin "2") (pinfunction "1_2") (pintype "passive"))
    )
    (net (code "111") (name "GPA2-2") (class "Default")
      (node (ref "IC2") (pin "23") (pinfunction "GPA2_23") (pintype "bidirectional"))
      (node (ref "RN9") (pin "2") (pinfunction "1_2") (pintype "passive"))
    )
    (net (code "112") (name "GPA2-3") (class "Default")
      (node (ref "IC3") (pin "23") (pinfunction "GPA2_23") (pintype "bidirectional"))
      (node (ref "RN17") (pin "2") (pinfunction "1_2") (pintype "passive"))
    )
    (net (code "113") (name "GPA2-4") (class "Default")
      (node (ref "IC4") (pin "23") (pinfunction "GPA2_23") (pintype "bidirectional"))
      (node (ref "RN25") (pin "2") (pinfunction "1_2") (pintype "passive"))
    )
    (net (code "114") (name "GPA2-5") (class "Default")
      (node (ref "IC5") (pin "23") (pinfunction "GPA2_23") (pintype "bidirectional"))
      (node (ref "RN33") (pin "2") (pinfunction "1_2") (pintype "passive"))
    )
    (net (code "115") (name "GPA2-6") (class "Default")
      (node (ref "IC6") (pin "23") (pinfunction "GPA2_23") (pintype "bidirectional"))
      (node (ref "RN37") (pin "2") (pinfunction "1_2") (pintype "passive"))
    )
    (net (code "116") (name "GPA3-1") (class "Default")
      (node (ref "IC1") (pin "24") (pinfunction "GPA3_24") (pintype "bidirectional"))
      (node (ref "RN1") (pin "1") (pinfunction "1_1") (pintype "passive"))
    )
    (net (code "117") (name "GPA3-2") (class "Default")
      (node (ref "IC2") (pin "24") (pinfunction "GPA3_24") (pintype "bidirectional"))
      (node (ref "RN9") (pin "1") (pinfunction "1_1") (pintype "passive"))
    )
    (net (code "118") (name "GPA3-3") (class "Default")
      (node (ref "IC3") (pin "24") (pinfunction "GPA3_24") (pintype "bidirectional"))
      (node (ref "RN17") (pin "1") (pinfunction "1_1") (pintype "passive"))
    )
    (net (code "119") (name "GPA3-4") (class "Default")
      (node (ref "IC4") (pin "24") (pinfunction "GPA3_24") (pintype "bidirectional"))
      (node (ref "RN25") (pin "1") (pinfunction "1_1") (pintype "passive"))
    )
    (net (code "120") (name "GPA3-5") (class "Default")
      (node (ref "IC5") (pin "24") (pinfunction "GPA3_24") (pintype "bidirectional"))
      (node (ref "RN33") (pin "1") (pinfunction "1_1") (pintype "passive"))
    )
    (net (code "121") (name "GPA3-6") (class "Default")
      (node (ref "IC6") (pin "24") (pinfunction "GPA3_24") (pintype "bidirectional"))
      (node (ref "RN37") (pin "1") (pinfunction "1_1") (pintype "passive"))
    )
    (net (code "122") (name "GPA4-1") (class "Default")
      (node (ref "IC1") (pin "25") (pinfunction "GPA4_25") (pintype "bidirectional"))
      (node (ref "RN2") (pin "4") (pinfunction "1_4") (pintype "passive"))
    )
    (net (code "123") (name "GPA4-2") (class "Default")
      (node (ref "IC2") (pin "25") (pinfunction "GPA4_25") (pintype "bidirectional"))
      (node (ref "RN10") (pin "4") (pinfunction "1_4") (pintype "passive"))
    )
    (net (code "124") (name "GPA4-3") (class "Default")
      (node (ref "IC3") (pin "25") (pinfunction "GPA4_25") (pintype "bidirectional"))
      (node (ref "RN18") (pin "4") (pinfunction "1_4") (pintype "passive"))
    )
    (net (code "125") (name "GPA4-4") (class "Default")
      (node (ref "IC4") (pin "25") (pinfunction "GPA4_25") (pintype "bidirectional"))
      (node (ref "RN26") (pin "4") (pinfunction "1_4") (pintype "passive"))
    )
    (net (code "126") (name "GPA4-5") (class "Default")
      (node (ref "IC5") (pin "25") (pinfunction "GPA4_25") (pintype "bidirectional"))
      (node (ref "RN34") (pin "4") (pinfunction "1_4") (pintype "passive"))
    )
    (net (code "127") (name "GPA4-6") (class "Default")
      (node (ref "IC6") (pin "25") (pinfunction "GPA4_25") (pintype "bidirectional"))
      (node (ref "RN38") (pin "4") (pinfunction "1_4") (pintype "passive"))
    )
    (net (code "128") (name "GPA5-1") (class "Default")
      (node (ref "IC1") (pin "26") (pinfunction "GPA5_26") (pintype "bidirectional"))
      (node (ref "RN2") (pin "3") (pinfunction "1_3") (pintype "passive"))
    )
    (net (code "129") (name "GPA5-2") (class "Default")
      (node (ref "IC2") (pin "26") (pinfunction "GPA5_26") (pintype "bidirectional"))
      (node (ref "RN10") (pin "3") (pinfunction "1_3") (pintype "passive"))
    )
    (net (code "130") (name "GPA5-3") (class "Default")
      (node (ref "IC3") (pin "26") (pinfunction "GPA5_26") (pintype "bidirectional"))
      (node (ref "RN18") (pin "3") (pinfunction "1_3") (pintype "passive"))
    )
    (net (code "131") (name "GPA5-4") (class "Default")
      (node (ref "IC4") (pin "26") (pinfunction "GPA5_26") (pintype "bidirectional"))
      (node (ref "RN26") (pin "3") (pinfunction "1_3") (pintype "passive"))
    )
    (net (code "132") (name "GPA5-5") (class "Default")
      (node (ref "IC5") (pin "26") (pinfunction "GPA5_26") (pintype "bidirectional"))
      (node (ref "RN34") (pin "3") (pinfunction "1_3") (pintype "passive"))
    )
    (net (code "133") (name "GPA5-6") (class "Default")
      (node (ref "IC6") (pin "26") (pinfunction "GPA5_26") (pintype "bidirectional"))
      (node (ref "RN38") (pin "3") (pinfunction "1_3") (pintype "passive"))
    )
    (net (code "134") (name "GPA6-1") (class "Default")
      (node (ref "IC1") (pin "27") (pinfunction "GPA6_27") (pintype "bidirectional"))
      (node (ref "RN2") (pin "2") (pinfunction "1_2") (pintype "passive"))
    )
    (net (code "135") (name "GPA6-2") (class "Default")
      (node (ref "IC2") (pin "27") (pinfunction "GPA6_27") (pintype "bidirectional"))
      (node (ref "RN10") (pin "2") (pinfunction "1_2") (pintype "passive"))
    )
    (net (code "136") (name "GPA6-3") (class "Default")
      (node (ref "IC3") (pin "27") (pinfunction "GPA6_27") (pintype "bidirectional"))
      (node (ref "RN18") (pin "2") (pinfunction "1_2") (pintype "passive"))
    )
    (net (code "137") (name "GPA6-4") (class "Default")
      (node (ref "IC4") (pin "27") (pinfunction "GPA6_27") (pintype "bidirectional"))
      (node (ref "RN26") (pin "2") (pinfunction "1_2") (pintype "passive"))
    )
    (net (code "138") (name "GPA6-5") (class "Default")
      (node (ref "IC5") (pin "27") (pinfunction "GPA6_27") (pintype "bidirectional"))
      (node (ref "RN34") (pin "2") (pinfunction "1_2") (pintype "passive"))
    )
    (net (code "139") (name "GPA6-6") (class "Default")
      (node (ref "IC6") (pin "27") (pinfunction "GPA6_27") (pintype "bidirectional"))
      (node (ref "RN38") (pin "2") (pinfunction "1_2") (pintype "passive"))
    )
    (net (code "140") (name "GPA7-1") (class "Default")
      (node (ref "IC1") (pin "28") (pinfunction "GPA7_28") (pintype "bidirectional"))
      (node (ref "RN2") (pin "1") (pinfunction "1_1") (pintype "passive"))
    )
    (net (code "141") (name "GPA7-2") (class "Default")
      (node (ref "IC2") (pin "28") (pinfunction "GPA7_28") (pintype "bidirectional"))
      (node (ref "RN10") (pin "1") (pinfunction "1_1") (pintype "passive"))
    )
    (net (code "142") (name "GPA7-3") (class "Default")
      (node (ref "IC3") (pin "28") (pinfunction "GPA7_28") (pintype "bidirectional"))
      (node (ref "RN18") (pin "1") (pinfunction "1_1") (pintype "passive"))
    )
    (net (code "143") (name "GPA7-4") (class "Default")
      (node (ref "IC4") (pin "28") (pinfunction "GPA7_28") (pintype "bidirectional"))
      (node (ref "RN26") (pin "1") (pinfunction "1_1") (pintype "passive"))
    )
    (net (code "144") (name "GPA7-5") (class "Default")
      (node (ref "IC5") (pin "28") (pinfunction "GPA7_28") (pintype "bidirectional"))
      (node (ref "RN34") (pin "1") (pinfunction "1_1") (pintype "passive"))
    )
    (net (code "145") (name "GPA7-6") (class "Default")
      (node (ref "IC6") (pin "28") (pinfunction "GPA7_28") (pintype "bidirectional"))
      (node (ref "RN38") (pin "1") (pinfunction "1_1") (pintype "passive"))
    )
    (net (code "146") (name "GPB0-1") (class "Default")
      (node (ref "IC1") (pin "1") (pinfunction "GPB0_1") (pintype "bidirectional"))
      (node (ref "RN3") (pin "4") (pinfunction "1_4") (pintype "passive"))
    )
    (net (code "147") (name "GPB0-2") (class "Default")
      (node (ref "IC2") (pin "1") (pinfunction "GPB0_1") (pintype "bidirectional"))
      (node (ref "RN11") (pin "4") (pinfunction "1_4") (pintype "passive"))
    )
    (net (code "148") (name "GPB0-3") (class "Default")
      (node (ref "IC3") (pin "1") (pinfunction "GPB0_1") (pintype "bidirectional"))
      (node (ref "RN19") (pin "4") (pinfunction "1_4") (pintype "passive"))
    )
    (net (code "149") (name "GPB0-4") (class "Default")
      (node (ref "IC4") (pin "1") (pinfunction "GPB0_1") (pintype "bidirectional"))
      (node (ref "RN27") (pin "4") (pinfunction "1_4") (pintype "passive"))
    )
    (net (code "150") (name "GPB0-5") (class "Default")
      (node (ref "IC5") (pin "1") (pinfunction "GPB0_1") (pintype "bidirectional"))
      (node (ref "RN35") (pin "4") (pinfunction "1_4") (pintype "passive"))
    )
    (net (code "151") (name "GPB0-6") (class "Default")
      (node (ref "IC6") (pin "1") (pinfunction "GPB0_1") (pintype "bidirectional"))
      (node (ref "RN39") (pin "4") (pinfunction "1_4") (pintype "passive"))
    )
    (net (code "152") (name "GPB1-1") (class "Default")
      (node (ref "IC1") (pin "2") (pinfunction "GPB1_2") (pintype "bidirectional"))
      (node (ref "RN3") (pin "3") (pinfunction "1_3") (pintype "passive"))
    )
    (net (code "153") (name "GPB1-2") (class "Default")
      (node (ref "IC2") (pin "2") (pinfunction "GPB1_2") (pintype "bidirectional"))
      (node (ref "RN11") (pin "3") (pinfunction "1_3") (pintype "passive"))
    )
    (net (code "154") (name "GPB1-3") (class "Default")
      (node (ref "IC3") (pin "2") (pinfunction "GPB1_2") (pintype "bidirectional"))
      (node (ref "RN19") (pin "3") (pinfunction "1_3") (pintype "passive"))
    )
    (net (code "155") (name "GPB1-4") (class "Default")
      (node (ref "IC4") (pin "2") (pinfunction "GPB1_2") (pintype "bidirectional"))
      (node (ref "RN27") (pin "3") (pinfunction "1_3") (pintype "passive"))
    )
    (net (code "156") (name "GPB1-5") (class "Default")
      (node (ref "IC5") (pin "2") (pinfunction "GPB1_2") (pintype "bidirectional"))
      (node (ref "RN35") (pin "3") (pinfunction "1_3") (pintype "passive"))
    )
    (net (code "157") (name "GPB1-6") (class "Default")
      (node (ref "IC6") (pin "2") (pinfunction "GPB1_2") (pintype "bidirectional"))
      (node (ref "RN39") (pin "3") (pinfunction "1_3") (pintype "passive"))
    )
    (net (code "158") (name "GPB2-1") (class "Default")
      (node (ref "IC1") (pin "3") (pinfunction "GPB2_3") (pintype "bidirectional"))
      (node (ref "RN3") (pin "2") (pinfunction "1_2") (pintype "passive"))
    )
    (net (code "159") (name "GPB2-2") (class "Default")
      (node (ref "IC2") (pin "3") (pinfunction "GPB2_3") (pintype "bidirectional"))
      (node (ref "RN11") (pin "2") (pinfunction "1_2") (pintype "passive"))
    )
    (net (code "160") (name "GPB2-3") (class "Default")
      (node (ref "IC3") (pin "3") (pinfunction "GPB2_3") (pintype "bidirectional"))
      (node (ref "RN19") (pin "2") (pinfunction "1_2") (pintype "passive"))
    )
    (net (code "161") (name "GPB2-4") (class "Default")
      (node (ref "IC4") (pin "3") (pinfunction "GPB2_3") (pintype "bidirectional"))
      (node (ref "RN27") (pin "2") (pinfunction "1_2") (pintype "passive"))
    )
    (net (code "162") (name "GPB2-5") (class "Default")
      (node (ref "IC5") (pin "3") (pinfunction "GPB2_3") (pintype "bidirectional"))
      (node (ref "RN35") (pin "2") (pinfunction "1_2") (pintype "passive"))
    )
    (net (code "163") (name "GPB2-6") (class "Default")
      (node (ref "IC6") (pin "3") (pinfunction "GPB2_3") (pintype "bidirectional"))
      (node (ref "RN39") (pin "2") (pinfunction "1_2") (pintype "passive"))
    )
    (net (code "164") (name "GPB3-1") (class "Default")
      (node (ref "IC1") (pin "4") (pinfunction "GPB3_4") (pintype "bidirectional"))
      (node (ref "RN3") (pin "1") (pinfunction "1_1") (pintype "passive"))
    )
    (net (code "165") (name "GPB3-2") (class "Default")
      (node (ref "IC2") (pin "4") (pinfunction "GPB3_4") (pintype "bidirectional"))
      (node (ref "RN11") (pin "1") (pinfunction "1_1") (pintype "passive"))
    )
    (net (code "166") (name "GPB3-3") (class "Default")
      (node (ref "IC3") (pin "4") (pinfunction "GPB3_4") (pintype "bidirectional"))
      (node (ref "RN19") (pin "1") (pinfunction "1_1") (pintype "passive"))
    )
    (net (code "167") (name "GPB3-4") (class "Default")
      (node (ref "IC4") (pin "4") (pinfunction "GPB3_4") (pintype "bidirectional"))
      (node (ref "RN27") (pin "1") (pinfunction "1_1") (pintype "passive"))
    )
    (net (code "168") (name "GPB3-5") (class "Default")
      (node (ref "IC5") (pin "4") (pinfunction "GPB3_4") (pintype "bidirectional"))
      (node (ref "RN35") (pin "1") (pinfunction "1_1") (pintype "passive"))
    )
    (net (code "169") (name "GPB3-6") (class "Default")
      (node (ref "IC6") (pin "4") (pinfunction "GPB3_4") (pintype "bidirectional"))
      (node (ref "RN39") (pin "1") (pinfunction "1_1") (pintype "passive"))
    )
    (net (code "170") (name "GPB4-1") (class "Default")
      (node (ref "IC1") (pin "5") (pinfunction "GPB4_5") (pintype "bidirectional"))
      (node (ref "RN4") (pin "4") (pinfunction "1_4") (pintype "passive"))
    )
    (net (code "171") (name "GPB4-2") (class "Default")
      (node (ref "IC2") (pin "5") (pinfunction "GPB4_5") (pintype "bidirectional"))
      (node (ref "RN12") (pin "4") (pinfunction "1_4") (pintype "passive"))
    )
    (net (code "172") (name "GPB4-3") (class "Default")
      (node (ref "IC3") (pin "5") (pinfunction "GPB4_5") (pintype "bidirectional"))
      (node (ref "RN20") (pin "4") (pinfunction "1_4") (pintype "passive"))
    )
    (net (code "173") (name "GPB4-4") (class "Default")
      (node (ref "IC4") (pin "5") (pinfunction "GPB4_5") (pintype "bidirectional"))
      (node (ref "RN28") (pin "4") (pinfunction "1_4") (pintype "passive"))
    )
    (net (code "174") (name "GPB4-5") (class "Default")
      (node (ref "IC5") (pin "5") (pinfunction "GPB4_5") (pintype "bidirectional"))
      (node (ref "RN36") (pin "4") (pinfunction "1_4") (pintype "passive"))
    )
    (net (code "175") (name "GPB4-6") (class "Default")
      (node (ref "IC6") (pin "5") (pinfunction "GPB4_5") (pintype "bidirectional"))
      (node (ref "RN40") (pin "4") (pinfunction "1_4") (pintype "passive"))
    )
    (net (code "176") (name "GPB5-1") (class "Default")
      (node (ref "IC1") (pin "6") (pinfunction "GPB5_6") (pintype "bidirectional"))
      (node (ref "RN4") (pin "3") (pinfunction "1_3") (pintype "passive"))
    )
    (net (code "177") (name "GPB5-2") (class "Default")
      (node (ref "IC2") (pin "6") (pinfunction "GPB5_6") (pintype "bidirectional"))
      (node (ref "RN12") (pin "3") (pinfunction "1_3") (pintype "passive"))
    )
    (net (code "178") (name "GPB5-3") (class "Default")
      (node (ref "IC3") (pin "6") (pinfunction "GPB5_6") (pintype "bidirectional"))
      (node (ref "RN20") (pin "3") (pinfunction "1_3") (pintype "passive"))
    )
    (net (code "179") (name "GPB5-4") (class "Default")
      (node (ref "IC4") (pin "6") (pinfunction "GPB5_6") (pintype "bidirectional"))
      (node (ref "RN28") (pin "3") (pinfunction "1_3") (pintype "passive"))
    )
    (net (code "180") (name "GPB5-5") (class "Default")
      (node (ref "IC5") (pin "6") (pinfunction "GPB5_6") (pintype "bidirectional"))
      (node (ref "RN36") (pin "3") (pinfunction "1_3") (pintype "passive"))
    )
    (net (code "181") (name "GPB5-6") (class "Default")
      (node (ref "IC6") (pin "6") (pinfunction "GPB5_6") (pintype "bidirectional"))
      (node (ref "RN40") (pin "3") (pinfunction "1_3") (pintype "passive"))
    )
    (net (code "182") (name "GPB6-1") (class "Default")
      (node (ref "IC1") (pin "7") (pinfunction "GPB6_7") (pintype "bidirectional"))
      (node (ref "RN4") (pin "2") (pinfunction "1_2") (pintype "passive"))
    )
    (net (code "183") (name "GPB6-2") (class "Default")
      (node (ref "IC2") (pin "7") (pinfunction "GPB6_7") (pintype "bidirectional"))
      (node (ref "RN12") (pin "2") (pinfunction "1_2") (pintype "passive"))
    )
    (net (code "184") (name "GPB6-3") (class "Default")
      (node (ref "IC3") (pin "7") (pinfunction "GPB6_7") (pintype "bidirectional"))
      (node (ref "RN20") (pin "2") (pinfunction "1_2") (pintype "passive"))
    )
    (net (code "185") (name "GPB6-4") (class "Default")
      (node (ref "IC4") (pin "7") (pinfunction "GPB6_7") (pintype "bidirectional"))
      (node (ref "RN28") (pin "2") (pinfunction "1_2") (pintype "passive"))
    )
    (net (code "186") (name "GPB6-5") (class "Default")
      (node (ref "IC5") (pin "7") (pinfunction "GPB6_7") (pintype "bidirectional"))
      (node (ref "RN36") (pin "2") (pinfunction "1_2") (pintype "passive"))
    )
    (net (code "187") (name "GPB6-6") (class "Default")
      (node (ref "IC6") (pin "7") (pinfunction "GPB6_7") (pintype "bidirectional"))
      (node (ref "RN40") (pin "2") (pinfunction "1_2") (pintype "passive"))
    )
    (net (code "188") (name "GPB7-1") (class "Default")
      (node (ref "IC1") (pin "8") (pinfunction "GPB7_8") (pintype "bidirectional"))
      (node (ref "RN4") (pin "1") (pinfunction "1_1") (pintype "passive"))
    )
    (net (code "189") (name "GPB7-2") (class "Default")
      (node (ref "IC2") (pin "8") (pinfunction "GPB7_8") (pintype "bidirectional"))
      (node (ref "RN12") (pin "1") (pinfunction "1_1") (pintype "passive"))
    )
    (net (code "190") (name "GPB7-3") (class "Default")
      (node (ref "IC3") (pin "8") (pinfunction "GPB7_8") (pintype "bidirectional"))
      (node (ref "RN20") (pin "1") (pinfunction "1_1") (pintype "passive"))
    )
    (net (code "191") (name "GPB7-4") (class "Default")
      (node (ref "IC4") (pin "8") (pinfunction "GPB7_8") (pintype "bidirectional"))
      (node (ref "RN28") (pin "1") (pinfunction "1_1") (pintype "passive"))
    )
    (net (code "192") (name "GPB7-5") (class "Default")
      (node (ref "IC5") (pin "8") (pinfunction "GPB7_8") (pintype "bidirectional"))
      (node (ref "RN36") (pin "1") (pinfunction "1_1") (pintype "passive"))
    )
    (net (code "193") (name "GPB7-6") (class "Default")
      (node (ref "IC6") (pin "8") (pinfunction "GPB7_8") (pintype "bidirectional"))
      (node (ref "RN40") (pin "1") (pinfunction "1_1") (pintype "passive"))
    )
    (net (code "194") (name "Net-(IC1-A0)") (class "Default")
      (node (ref "IC1") (pin "15") (pinfunction "A0_15") (pintype "input"))
      (node (ref "J7") (pin "2") (pinfunction "2_2") (pintype "passive"))
      (node (ref "RN49") (pin "6") (pinfunction "2_6") (pintype "passive"))
    )
    (net (code "195") (name "Net-(IC1-A1)") (class "Default")
      (node (ref "IC1") (pin "16") (pinfunction "A1_16") (pintype "input"))
      (node (ref "J7") (pin "4") (pinfunction "4_4") (pintype "passive"))
      (node (ref "RN49") (pin "7") (pinfunction "2_7") (pintype "passive"))
    )
    (net (code "196") (name "Net-(IC1-A2)") (class "Default")
      (node (ref "IC1") (pin "17") (pinfunction "A2_17") (pintype "input"))
      (node (ref "J7") (pin "6") (pinfunction "6_6") (pintype "passive"))
      (node (ref "RN49") (pin "8") (pinfunction "2_8") (pintype "passive"))
    )
    (net (code "197") (name "Net-(IC2-A0)") (class "Default")
      (node (ref "IC2") (pin "15") (pinfunction "A0_15") (pintype "input"))
      (node (ref "J12") (pin "2") (pinfunction "2_2") (pintype "passive"))
      (node (ref "RN50") (pin "6") (pinfunction "2_6") (pintype "passive"))
    )
    (net (code "198") (name "Net-(IC2-A1)") (class "Default")
      (node (ref "IC2") (pin "16") (pinfunction "A1_16") (pintype "input"))
      (node (ref "J12") (pin "4") (pinfunction "4_4") (pintype "passive"))
      (node (ref "RN50") (pin "7") (pinfunction "2_7") (pintype "passive"))
    )
    (net (code "199") (name "Net-(IC2-A2)") (class "Default")
      (node (ref "IC2") (pin "17") (pinfunction "A2_17") (pintype "input"))
      (node (ref "J12") (pin "6") (pinfunction "6_6") (pintype "passive"))
      (node (ref "RN50") (pin "8") (pinfunction "2_8") (pintype "passive"))
    )
    (net (code "200") (name "Net-(IC3-A0)") (class "Default")
      (node (ref "IC3") (pin "15") (pinfunction "A0_15") (pintype "input"))
      (node (ref "J11") (pin "2") (pinfunction "2_2") (pintype "passive"))
      (node (ref "RN51") (pin "6") (pinfunction "2_6") (pintype "passive"))
    )
    (net (code "201") (name "Net-(IC3-A1)") (class "Default")
      (node (ref "IC3") (pin "16") (pinfunction "A1_16") (pintype "input"))
      (node (ref "J11") (pin "4") (pinfunction "4_4") (pintype "passive"))
      (node (ref "RN51") (pin "7") (pinfunction "2_7") (pintype "passive"))
    )
    (net (code "202") (name "Net-(IC3-A2)") (class "Default")
      (node (ref "IC3") (pin "17") (pinfunction "A2_17") (pintype "input"))
      (node (ref "J11") (pin "6") (pinfunction "6_6") (pintype "passive"))
      (node (ref "RN51") (pin "8") (pinfunction "2_8") (pintype "passive"))
    )
    (net (code "203") (name "Net-(IC4-A0)") (class "Default")
      (node (ref "IC4") (pin "15") (pinfunction "A0_15") (pintype "input"))
      (node (ref "J10") (pin "2") (pinfunction "2_2") (pintype "passive"))
      (node (ref "RN52") (pin "6") (pinfunction "2_6") (pintype "passive"))
    )
    (net (code "204") (name "Net-(IC4-A1)") (class "Default")
      (node (ref "IC4") (pin "16") (pinfunction "A1_16") (pintype "input"))
      (node (ref "J10") (pin "4") (pinfunction "4_4") (pintype "passive"))
      (node (ref "RN52") (pin "7") (pinfunction "2_7") (pintype "passive"))
    )
    (net (code "205") (name "Net-(IC4-A2)") (class "Default")
      (node (ref "IC4") (pin "17") (pinfunction "A2_17") (pintype "input"))
      (node (ref "J10") (pin "6") (pinfunction "6_6") (pintype "passive"))
      (node (ref "RN52") (pin "8") (pinfunction "2_8") (pintype "passive"))
    )
    (net (code "206") (name "Net-(IC5-A0)") (class "Default")
      (node (ref "IC5") (pin "15") (pinfunction "A0_15") (pintype "input"))
      (node (ref "J9") (pin "2") (pinfunction "2_2") (pintype "passive"))
      (node (ref "RN53") (pin "6") (pinfunction "2_6") (pintype "passive"))
    )
    (net (code "207") (name "Net-(IC5-A1)") (class "Default")
      (node (ref "IC5") (pin "16") (pinfunction "A1_16") (pintype "input"))
      (node (ref "J9") (pin "4") (pinfunction "4_4") (pintype "passive"))
      (node (ref "RN53") (pin "7") (pinfunction "2_7") (pintype "passive"))
    )
    (net (code "208") (name "Net-(IC5-A2)") (class "Default")
      (node (ref "IC5") (pin "17") (pinfunction "A2_17") (pintype "input"))
      (node (ref "J9") (pin "6") (pinfunction "6_6") (pintype "passive"))
      (node (ref "RN53") (pin "8") (pinfunction "2_8") (pintype "passive"))
    )
    (net (code "209") (name "Net-(IC6-A0)") (class "Default")
      (node (ref "IC6") (pin "15") (pinfunction "A0_15") (pintype "input"))
      (node (ref "J8") (pin "2") (pinfunction "2_2") (pintype "passive"))
      (node (ref "RN54") (pin "6") (pinfunction "2_6") (pintype "passive"))
    )
    (net (code "210") (name "Net-(IC6-A1)") (class "Default")
      (node (ref "IC6") (pin "16") (pinfunction "A1_16") (pintype "input"))
      (node (ref "J8") (pin "4") (pinfunction "4_4") (pintype "passive"))
      (node (ref "RN54") (pin "7") (pinfunction "2_7") (pintype "passive"))
    )
    (net (code "211") (name "Net-(IC6-A2)") (class "Default")
      (node (ref "IC6") (pin "17") (pinfunction "A2_17") (pintype "input"))
      (node (ref "J8") (pin "6") (pinfunction "6_6") (pintype "passive"))
      (node (ref "RN54") (pin "8") (pinfunction "2_8") (pintype "passive"))
    )
    (net (code "212") (name "Net-(LED1-PadA)") (class "Default")
      (node (ref "LED1") (pin "A") (pinfunction "A_A") (pintype "passive"))
      (node (ref "R98") (pin "1") (pinfunction "1_1") (pintype "passive"))
    )
    (net (code "213") (name "Net-(LED2-PadA)") (class "Default")
      (node (ref "LED2") (pin "A") (pinfunction "A_A") (pintype "passive"))
      (node (ref "R97") (pin "1") (pinfunction "1_1") (pintype "passive"))
    )
    (net (code "214") (name "Net-(R99-Pad2)") (class "Default")
      (node (ref "R99") (pin "2") (pinfunction "2_2") (pintype "passive"))
      (node (ref "SJ2") (pin "1") (pinfunction "1_1") (pintype "passive"))
    )
    (net (code "215") (name "Net-(R100-Pad2)") (class "Default")
      (node (ref "R100") (pin "2") (pinfunction "2_2") (pintype "passive"))
      (node (ref "SJ1") (pin "1") (pinfunction "1_1") (pintype "passive"))
    )
    (net (code "216") (name "Net-(R101-Pad2)") (class "Default")
      (node (ref "R101") (pin "2") (pinfunction "2_2") (pintype "passive"))
      (node (ref "SJ3") (pin "1") (pinfunction "1_1") (pintype "passive"))
    )
    (net (code "217") (name "SCL") (class "Default")
      (node (ref "IC1") (pin "12") (pinfunction "SCL_12") (pintype "input"))
      (node (ref "IC2") (pin "12") (pinfunction "SCL_12") (pintype "input"))
      (node (ref "IC3") (pin "12") (pinfunction "SCL_12") (pintype "input"))
      (node (ref "IC4") (pin "12") (pinfunction "SCL_12") (pintype "input"))
      (node (ref "IC5") (pin "12") (pinfunction "SCL_12") (pintype "input"))
      (node (ref "IC6") (pin "12") (pinfunction "SCL_12") (pintype "input"))
      (node (ref "J1") (pin "1") (pinfunction "1_1") (pintype "passive"))
      (node (ref "J2") (pin "1") (pinfunction "1_1") (pintype "passive"))
      (node (ref "R99") (pin "1") (pinfunction "1_1") (pintype "passive"))
    )
    (net (code "218") (name "SDA") (class "Default")
      (node (ref "IC1") (pin "13") (pinfunction "SDA_13") (pintype "bidirectional"))
      (node (ref "IC2") (pin "13") (pinfunction "SDA_13") (pintype "bidirectional"))
      (node (ref "IC3") (pin "13") (pinfunction "SDA_13") (pintype "bidirectional"))
      (node (ref "IC4") (pin "13") (pinfunction "SDA_13") (pintype "bidirectional"))
      (node (ref "IC5") (pin "13") (pinfunction "SDA_13") (pintype "bidirectional"))
      (node (ref "IC6") (pin "13") (pinfunction "SDA_13") (pintype "bidirectional"))
      (node (ref "J1") (pin "2") (pinfunction "2_2") (pintype "passive"))
      (node (ref "J2") (pin "2") (pinfunction "2_2") (pintype "passive"))
      (node (ref "R100") (pin "1") (pinfunction "1_1") (pintype "passive"))
    )
    (net (code "219") (name "VCC") (class "Default")
      (node (ref "C1") (pin "1") (pinfunction "1_1") (pintype "passive"))
      (node (ref "C2") (pin "1") (pinfunction "1_1") (pintype "passive"))
      (node (ref "C3") (pin "1") (pinfunction "1_1") (pintype "passive"))
      (node (ref "C4") (pin "1") (pinfunction "1_1") (pintype "passive"))
      (node (ref "C5") (pin "1") (pinfunction "1_1") (pintype "passive"))
      (node (ref "C6") (pin "1") (pinfunction "1_1") (pintype "passive"))
      (node (ref "IC1") (pin "9") (pinfunction "VDD_9") (pintype "power_in"))
      (node (ref "IC2") (pin "9") (pinfunction "VDD_9") (pintype "power_in"))
      (node (ref "IC3") (pin "9") (pinfunction "VDD_9") (pintype "power_in"))
      (node (ref "IC4") (pin "9") (pinfunction "VDD_9") (pintype "power_in"))
      (node (ref "IC5") (pin "9") (pinfunction "VDD_9") (pintype "power_in"))
      (node (ref "IC6") (pin "9") (pinfunction "VDD_9") (pintype "power_in"))
      (node (ref "J1") (pin "5") (pinfunction "5_5") (pintype "passive"))
      (node (ref "J10") (pin "1") (pinfunction "1_1") (pintype "passive"))
      (node (ref "J10") (pin "3") (pinfunction "3_3") (pintype "passive"))
      (node (ref "J10") (pin "5") (pinfunction "5_5") (pintype "passive"))
      (node (ref "J11") (pin "1") (pinfunction "1_1") (pintype "passive"))
      (node (ref "J11") (pin "3") (pinfunction "3_3") (pintype "passive"))
      (node (ref "J11") (pin "5") (pinfunction "5_5") (pintype "passive"))
      (node (ref "J12") (pin "1") (pinfunction "1_1") (pintype "passive"))
      (node (ref "J12") (pin "3") (pinfunction "3_3") (pintype "passive"))
      (node (ref "J12") (pin "5") (pinfunction "5_5") (pintype "passive"))
      (node (ref "J2") (pin "5") (pinfunction "5_5") (pintype "passive"))
      (node (ref "J7") (pin "1") (pinfunction "1_1") (pintype "passive"))
      (node (ref "J7") (pin "3") (pinfunction "3_3") (pintype "passive"))
      (node (ref "J7") (pin "5") (pinfunction "5_5") (pintype "passive"))
      (node (ref "J8") (pin "1") (pinfunction "1_1") (pintype "passive"))
      (node (ref "J8") (pin "3") (pinfunction "3_3") (pintype "passive"))
      (node (ref "J8") (pin "5") (pinfunction "5_5") (pintype "passive"))
      (node (ref "J9") (pin "1") (pinfunction "1_1") (pintype "passive"))
      (node (ref "J9") (pin "3") (pinfunction "3_3") (pintype "passive"))
      (node (ref "J9") (pin "5") (pinfunction "5_5") (pintype "passive"))
      (node (ref "R97") (pin "2") (pinfunction "2_2") (pintype "passive"))
      (node (ref "RN13") (pin "5") (pinfunction "2_5") (pintype "passive"))
      (node (ref "RN13") (pin "6") (pinfunction "2_6") (pintype "passive"))
      (node (ref "RN13") (pin "7") (pinfunction "2_7") (pintype "passive"))
      (node (ref "RN13") (pin "8") (pinfunction "2_8") (pintype "passive"))
      (node (ref "RN14") (pin "5") (pinfunction "2_5") (pintype "passive"))
      (node (ref "RN14") (pin "6") (pinfunction "2_6") (pintype "passive"))
      (node (ref "RN14") (pin "7") (pinfunction "2_7") (pintype "passive"))
      (node (ref "RN14") (pin "8") (pinfunction "2_8") (pintype "passive"))
      (node (ref "RN15") (pin "5") (pinfunction "2_5") (pintype "passive"))
      (node (ref "RN15") (pin "6") (pinfunction "2_6") (pintype "passive"))
      (node (ref "RN15") (pin "7") (pinfunction "2_7") (pintype "passive"))
      (node (ref "RN15") (pin "8") (pinfunction "2_8") (pintype "passive"))
      (node (ref "RN16") (pin "5") (pinfunction "2_5") (pintype "passive"))
      (node (ref "RN16") (pin "6") (pinfunction "2_6") (pintype "passive"))
      (node (ref "RN16") (pin "7") (pinfunction "2_7") (pintype "passive"))
      (node (ref "RN16") (pin "8") (pinfunction "2_8") (pintype "passive"))
      (node (ref "RN21") (pin "5") (pinfunction "2_5") (pintype "passive"))
      (node (ref "RN21") (pin "6") (pinfunction "2_6") (pintype "passive"))
      (node (ref "RN21") (pin "7") (pinfunction "2_7") (pintype "passive"))
      (node (ref "RN21") (pin "8") (pinfunction "2_8") (pintype "passive"))
      (node (ref "RN22") (pin "5") (pinfunction "2_5") (pintype "passive"))
      (node (ref "RN22") (pin "6") (pinfunction "2_6") (pintype "passive"))
      (node (ref "RN22") (pin "7") (pinfunction "2_7") (pintype "passive"))
      (node (ref "RN22") (pin "8") (pinfunction "2_8") (pintype "passive"))
      (node (ref "RN23") (pin "5") (pinfunction "2_5") (pintype "passive"))
      (node (ref "RN23") (pin "6") (pinfunction "2_6") (pintype "passive"))
      (node (ref "RN23") (pin "7") (pinfunction "2_7") (pintype "passive"))
      (node (ref "RN23") (pin "8") (pinfunction "2_8") (pintype "passive"))
      (node (ref "RN24") (pin "5") (pinfunction "2_5") (pintype "passive"))
      (node (ref "RN24") (pin "6") (pinfunction "2_6") (pintype "passive"))
      (node (ref "RN24") (pin "7") (pinfunction "2_7") (pintype "passive"))
      (node (ref "RN24") (pin "8") (pinfunction "2_8") (pintype "passive"))
      (node (ref "RN29") (pin "5") (pinfunction "2_5") (pintype "passive"))
      (node (ref "RN29") (pin "6") (pinfunction "2_6") (pintype "passive"))
      (node (ref "RN29") (pin "7") (pinfunction "2_7") (pintype "passive"))
      (node (ref "RN29") (pin "8") (pinfunction "2_8") (pintype "passive"))
      (node (ref "RN30") (pin "5") (pinfunction "2_5") (pintype "passive"))
      (node (ref "RN30") (pin "6") (pinfunction "2_6") (pintype "passive"))
      (node (ref "RN30") (pin "7") (pinfunction "2_7") (pintype "passive"))
      (node (ref "RN30") (pin "8") (pinfunction "2_8") (pintype "passive"))
      (node (ref "RN31") (pin "5") (pinfunction "2_5") (pintype "passive"))
      (node (ref "RN31") (pin "6") (pinfunction "2_6") (pintype "passive"))
      (node (ref "RN31") (pin "7") (pinfunction "2_7") (pintype "passive"))
      (node (ref "RN31") (pin "8") (pinfunction "2_8") (pintype "passive"))
      (node (ref "RN32") (pin "5") (pinfunction "2_5") (pintype "passive"))
      (node (ref "RN32") (pin "6") (pinfunction "2_6") (pintype "passive"))
      (node (ref "RN32") (pin "7") (pinfunction "2_7") (pintype "passive"))
      (node (ref "RN32") (pin "8") (pinfunction "2_8") (pintype "passive"))
      (node (ref "RN41") (pin "5") (pinfunction "2_5") (pintype "passive"))
      (node (ref "RN41") (pin "6") (pinfunction "2_6") (pintype "passive"))
      (node (ref "RN41") (pin "7") (pinfunction "2_7") (pintype "passive"))
      (node (ref "RN41") (pin "8") (pinfunction "2_8") (pintype "passive"))
      (node (ref "RN42") (pin "5") (pinfunction "2_5") (pintype "passive"))
      (node (ref "RN42") (pin "6") (pinfunction "2_6") (pintype "passive"))
      (node (ref "RN42") (pin "7") (pinfunction "2_7") (pintype "passive"))
      (node (ref "RN42") (pin "8") (pinfunction "2_8") (pintype "passive"))
      (node (ref "RN43") (pin "5") (pinfunction "2_5") (pintype "passive"))
      (node (ref "RN43") (pin "6") (pinfunction "2_6") (pintype "passive"))
      (node (ref "RN43") (pin "7") (pinfunction "2_7") (pintype "passive"))
      (node (ref "RN43") (pin "8") (pinfunction "2_8") (pintype "passive"))
      (node (ref "RN44") (pin "5") (pinfunction "2_5") (pintype "passive"))
      (node (ref "RN44") (pin "6") (pinfunction "2_6") (pintype "passive"))
      (node (ref "RN44") (pin "7") (pinfunction "2_7") (pintype "passive"))
      (node (ref "RN44") (pin "8") (pinfunction "2_8") (pintype "passive"))
      (node (ref "RN45") (pin "5") (pinfunction "2_5") (pintype "passive"))
      (node (ref "RN45") (pin "6") (pinfunction "2_6") (pintype "passive"))
      (node (ref "RN45") (pin "7") (pinfunction "2_7") (pintype "passive"))
      (node (ref "RN45") (pin "8") (pinfunction "2_8") (pintype "passive"))
      (node (ref "RN46") (pin "5") (pinfunction "2_5") (pintype "passive"))
      (node (ref "RN46") (pin "6") (pinfunction "2_6") (pintype "passive"))
      (node (ref "RN46") (pin "7") (pinfunction "2_7") (pintype "passive"))
      (node (ref "RN46") (pin "8") (pinfunction "2_8") (pintype "passive"))
      (node (ref "RN47") (pin "5") (pinfunction "2_5") (pintype "passive"))
      (node (ref "RN47") (pin "6") (pinfunction "2_6") (pintype "passive"))
      (node (ref "RN47") (pin "7") (pinfunction "2_7") (pintype "passive"))
      (node (ref "RN47") (pin "8") (pinfunction "2_8") (pintype "passive"))
      (node (ref "RN48") (pin "5") (pinfunction "2_5") (pintype "passive"))
      (node (ref "RN48") (pin "6") (pinfunction "2_6") (pintype "passive"))
      (node (ref "RN48") (pin "7") (pinfunction "2_7") (pintype "passive"))
      (node (ref "RN48") (pin "8") (pinfunction "2_8") (pintype "passive"))
      (node (ref "RN5") (pin "5") (pinfunction "2_5") (pintype "passive"))
      (node (ref "RN5") (pin "6") (pinfunction "2_6") (pintype "passive"))
      (node (ref "RN5") (pin "7") (pinfunction "2_7") (pintype "passive"))
      (node (ref "RN5") (pin "8") (pinfunction "2_8") (pintype "passive"))
      (node (ref "RN6") (pin "5") (pinfunction "2_5") (pintype "passive"))
      (node (ref "RN6") (pin "6") (pinfunction "2_6") (pintype "passive"))
      (node (ref "RN6") (pin "7") (pinfunction "2_7") (pintype "passive"))
      (node (ref "RN6") (pin "8") (pinfunction "2_8") (pintype "passive"))
      (node (ref "RN7") (pin "5") (pinfunction "2_5") (pintype "passive"))
      (node (ref "RN7") (pin "6") (pinfunction "2_6") (pintype "passive"))
      (node (ref "RN7") (pin "7") (pinfunction "2_7") (pintype "passive"))
      (node (ref "RN7") (pin "8") (pinfunction "2_8") (pintype "passive"))
      (node (ref "RN8") (pin "5") (pinfunction "2_5") (pintype "passive"))
      (node (ref "RN8") (pin "6") (pinfunction "2_6") (pintype "passive"))
      (node (ref "RN8") (pin "7") (pinfunction "2_7") (pintype "passive"))
      (node (ref "RN8") (pin "8") (pinfunction "2_8") (pintype "passive"))
      (node (ref "SJ1") (pin "2") (pinfunction "2_2") (pintype "passive"))
      (node (ref "SJ2") (pin "2") (pinfunction "2_2") (pintype "passive"))
      (node (ref "SJ3") (pin "2") (pinfunction "2_2") (pintype "passive"))
    )
    (net (code "220") (name "VIN") (class "Default")
      (node (ref "C7") (pin "+") (pinfunction "+_+") (pintype "passive"))
      (node (ref "C8") (pin "+") (pinfunction "+_+") (pintype "passive"))
      (node (ref "C9") (pin "+") (pinfunction "+_+") (pintype "passive"))
      (node (ref "J1") (pin "3") (pinfunction "3_3") (pintype "passive"))
      (node (ref "J2") (pin "3") (pinfunction "3_3") (pintype "passive"))
      (node (ref "J4") (pin "A4") (pinfunction "A4_A4") (pintype "bidirectional"))
      (node (ref "J4") (pin "A5") (pinfunction "A5_A5") (pintype "bidirectional"))
      (node (ref "J4") (pin "B4") (pinfunction "B4_B4") (pintype "bidirectional"))
      (node (ref "J4") (pin "B5") (pinfunction "B5_B5") (pintype "bidirectional"))
      (node (ref "J4") (pin "C4") (pinfunction "C4_C4") (pintype "bidirectional"))
      (node (ref "J4") (pin "C5") (pinfunction "C5_C5") (pintype "bidirectional"))
      (node (ref "J4") (pin "D4") (pinfunction "D4_D4") (pintype "bidirectional"))
      (node (ref "J4") (pin "D5") (pinfunction "D5_D5") (pintype "bidirectional"))
      (node (ref "J4") (pin "E4") (pinfunction "E4_E4") (pintype "bidirectional"))
      (node (ref "J4") (pin "E5") (pinfunction "E5_E5") (pintype "bidirectional"))
      (node (ref "J4") (pin "F4") (pinfunction "F4_F4") (pintype "bidirectional"))
      (node (ref "J4") (pin "F5") (pinfunction "F5_F5") (pintype "bidirectional"))
      (node (ref "J4") (pin "G4") (pinfunction "G4_G4") (pintype "bidirectional"))
      (node (ref "J4") (pin "G5") (pinfunction "G5_G5") (pintype "bidirectional"))
      (node (ref "J4") (pin "H4") (pinfunction "H4_H4") (pintype "bidirectional"))
      (node (ref "J4") (pin "H5") (pinfunction "H5_H5") (pintype "bidirectional"))
      (node (ref "J5") (pin "A4") (pinfunction "A4_A4") (pintype "bidirectional"))
      (node (ref "J5") (pin "A5") (pinfunction "A5_A5") (pintype "bidirectional"))
      (node (ref "J5") (pin "B4") (pinfunction "B4_B4") (pintype "bidirectional"))
      (node (ref "J5") (pin "B5") (pinfunction "B5_B5") (pintype "bidirectional"))
      (node (ref "J5") (pin "C4") (pinfunction "C4_C4") (pintype "bidirectional"))
      (node (ref "J5") (pin "C5") (pinfunction "C5_C5") (pintype "bidirectional"))
      (node (ref "J5") (pin "D4") (pinfunction "D4_D4") (pintype "bidirectional"))
      (node (ref "J5") (pin "D5") (pinfunction "D5_D5") (pintype "bidirectional"))
      (node (ref "J5") (pin "E4") (pinfunction "E4_E4") (pintype "bidirectional"))
      (node (ref "J5") (pin "E5") (pinfunction "E5_E5") (pintype "bidirectional"))
      (node (ref "J5") (pin "F4") (pinfunction "F4_F4") (pintype "bidirectional"))
      (node (ref "J5") (pin "F5") (pinfunction "F5_F5") (pintype "bidirectional"))
      (node (ref "J5") (pin "G4") (pinfunction "G4_G4") (pintype "bidirectional"))
      (node (ref "J5") (pin "G5") (pinfunction "G5_G5") (pintype "bidirectional"))
      (node (ref "J5") (pin "H4") (pinfunction "H4_H4") (pintype "bidirectional"))
      (node (ref "J5") (pin "H5") (pinfunction "H5_H5") (pintype "bidirectional"))
      (node (ref "J6") (pin "A4") (pinfunction "A4_A4") (pintype "bidirectional"))
      (node (ref "J6") (pin "A5") (pinfunction "A5_A5") (pintype "bidirectional"))
      (node (ref "J6") (pin "B4") (pinfunction "B4_B4") (pintype "bidirectional"))
      (node (ref "J6") (pin "B5") (pinfunction "B5_B5") (pintype "bidirectional"))
      (node (ref "J6") (pin "C4") (pinfunction "C4_C4") (pintype "bidirectional"))
      (node (ref "J6") (pin "C5") (pinfunction "C5_C5") (pintype "bidirectional"))
      (node (ref "J6") (pin "D4") (pinfunction "D4_D4") (pintype "bidirectional"))
      (node (ref "J6") (pin "D5") (pinfunction "D5_D5") (pintype "bidirectional"))
      (node (ref "J6") (pin "E4") (pinfunction "E4_E4") (pintype "bidirectional"))
      (node (ref "J6") (pin "E5") (pinfunction "E5_E5") (pintype "bidirectional"))
      (node (ref "J6") (pin "F4") (pinfunction "F4_F4") (pintype "bidirectional"))
      (node (ref "J6") (pin "F5") (pinfunction "F5_F5") (pintype "bidirectional"))
      (node (ref "J6") (pin "G4") (pinfunction "G4_G4") (pintype "bidirectional"))
      (node (ref "J6") (pin "G5") (pinfunction "G5_G5") (pintype "bidirectional"))
      (node (ref "J6") (pin "H4") (pinfunction "H4_H4") (pintype "bidirectional"))
      (node (ref "J6") (pin "H5") (pinfunction "H5_H5") (pintype "bidirectional"))
      (node (ref "R98") (pin "2") (pinfunction "2_2") (pintype "passive"))
    )
    (net (code "221") (name "unconnected-(IC1-INTB-Pad19)") (class "Default")
      (node (ref "IC1") (pin "19") (pinfunction "INTB_19") (pintype "output"))
    )
    (net (code "222") (name "unconnected-(IC2-INTB-Pad19)") (class "Default")
      (node (ref "IC2") (pin "19") (pinfunction "INTB_19") (pintype "output"))
    )
    (net (code "223") (name "unconnected-(IC3-INTB-Pad19)") (class "Default")
      (node (ref "IC3") (pin "19") (pinfunction "INTB_19") (pintype "output"))
    )
    (net (code "224") (name "unconnected-(IC4-INTB-Pad19)") (class "Default")
      (node (ref "IC4") (pin "19") (pinfunction "INTB_19") (pintype "output"))
    )
    (net (code "225") (name "unconnected-(IC5-INTB-Pad19)") (class "Default")
      (node (ref "IC5") (pin "19") (pinfunction "INTB_19") (pintype "output"))
    )
    (net (code "226") (name "unconnected-(IC6-INTB-Pad19)") (class "Default")
      (node (ref "IC6") (pin "19") (pinfunction "INTB_19") (pintype "output"))
    )
    (net (code "227") (name "unconnected-(RN49D-2-Pad5)") (class "Default")
      (node (ref "RN49") (pin "5") (pinfunction "2_5") (pintype "passive"))
    )
    (net (code "228") (name "unconnected-(RN50D-2-Pad5)") (class "Default")
      (node (ref "RN50") (pin "5") (pinfunction "2_5") (pintype "passive"))
    )
    (net (code "229") (name "unconnected-(RN51D-2-Pad5)") (class "Default")
      (node (ref "RN51") (pin "5") (pinfunction "2_5") (pintype "passive"))
    )
    (net (code "230") (name "unconnected-(RN52D-2-Pad5)") (class "Default")
      (node (ref "RN52") (pin "5") (pinfunction "2_5") (pintype "passive"))
    )
    (net (code "231") (name "unconnected-(RN53D-2-Pad5)") (class "Default")
      (node (ref "RN53") (pin "5") (pinfunction "2_5") (pintype "passive"))
    )
    (net (code "232") (name "unconnected-(RN54D-2-Pad5)") (class "Default")
      (node (ref "RN54") (pin "5") (pinfunction "2_5") (pintype "passive"))
    )
    (net (code "233") (name "~{INT}") (class "Default")
      (node (ref "IC1") (pin "20") (pinfunction "INTA_20") (pintype "output"))
      (node (ref "IC2") (pin "20") (pinfunction "INTA_20") (pintype "output"))
      (node (ref "IC3") (pin "20") (pinfunction "INTA_20") (pintype "output"))
      (node (ref "IC4") (pin "20") (pinfunction "INTA_20") (pintype "output"))
      (node (ref "IC5") (pin "20") (pinfunction "INTA_20") (pintype "output"))
      (node (ref "IC6") (pin "20") (pinfunction "INTA_20") (pintype "output"))
      (node (ref "J3") (pin "1") (pinfunction "1_1") (pintype "passive"))
    )
    (net (code "234") (name "~{RESET}") (class "Default")
      (node (ref "IC1") (pin "18") (pinfunction "~{RESET}_18") (pintype "input"))
      (node (ref "IC2") (pin "18") (pinfunction "~{RESET}_18") (pintype "input"))
      (node (ref "IC3") (pin "18") (pinfunction "~{RESET}_18") (pintype "input"))
      (node (ref "IC4") (pin "18") (pinfunction "~{RESET}_18") (pintype "input"))
      (node (ref "IC5") (pin "18") (pinfunction "~{RESET}_18") (pintype "input"))
      (node (ref "IC6") (pin "18") (pinfunction "~{RESET}_18") (pintype "input"))
      (node (ref "J1") (pin "6") (pinfunction "6_6") (pintype "passive"))
      (node (ref "J2") (pin "6") (pinfunction "6_6") (pintype "passive"))
      (node (ref "R101") (pin "1") (pinfunction "1_1") (pintype "passive"))
    )
  )
)
